# MARK-II_board.net
KiCad netlist of a schematic drawn in EAGLE
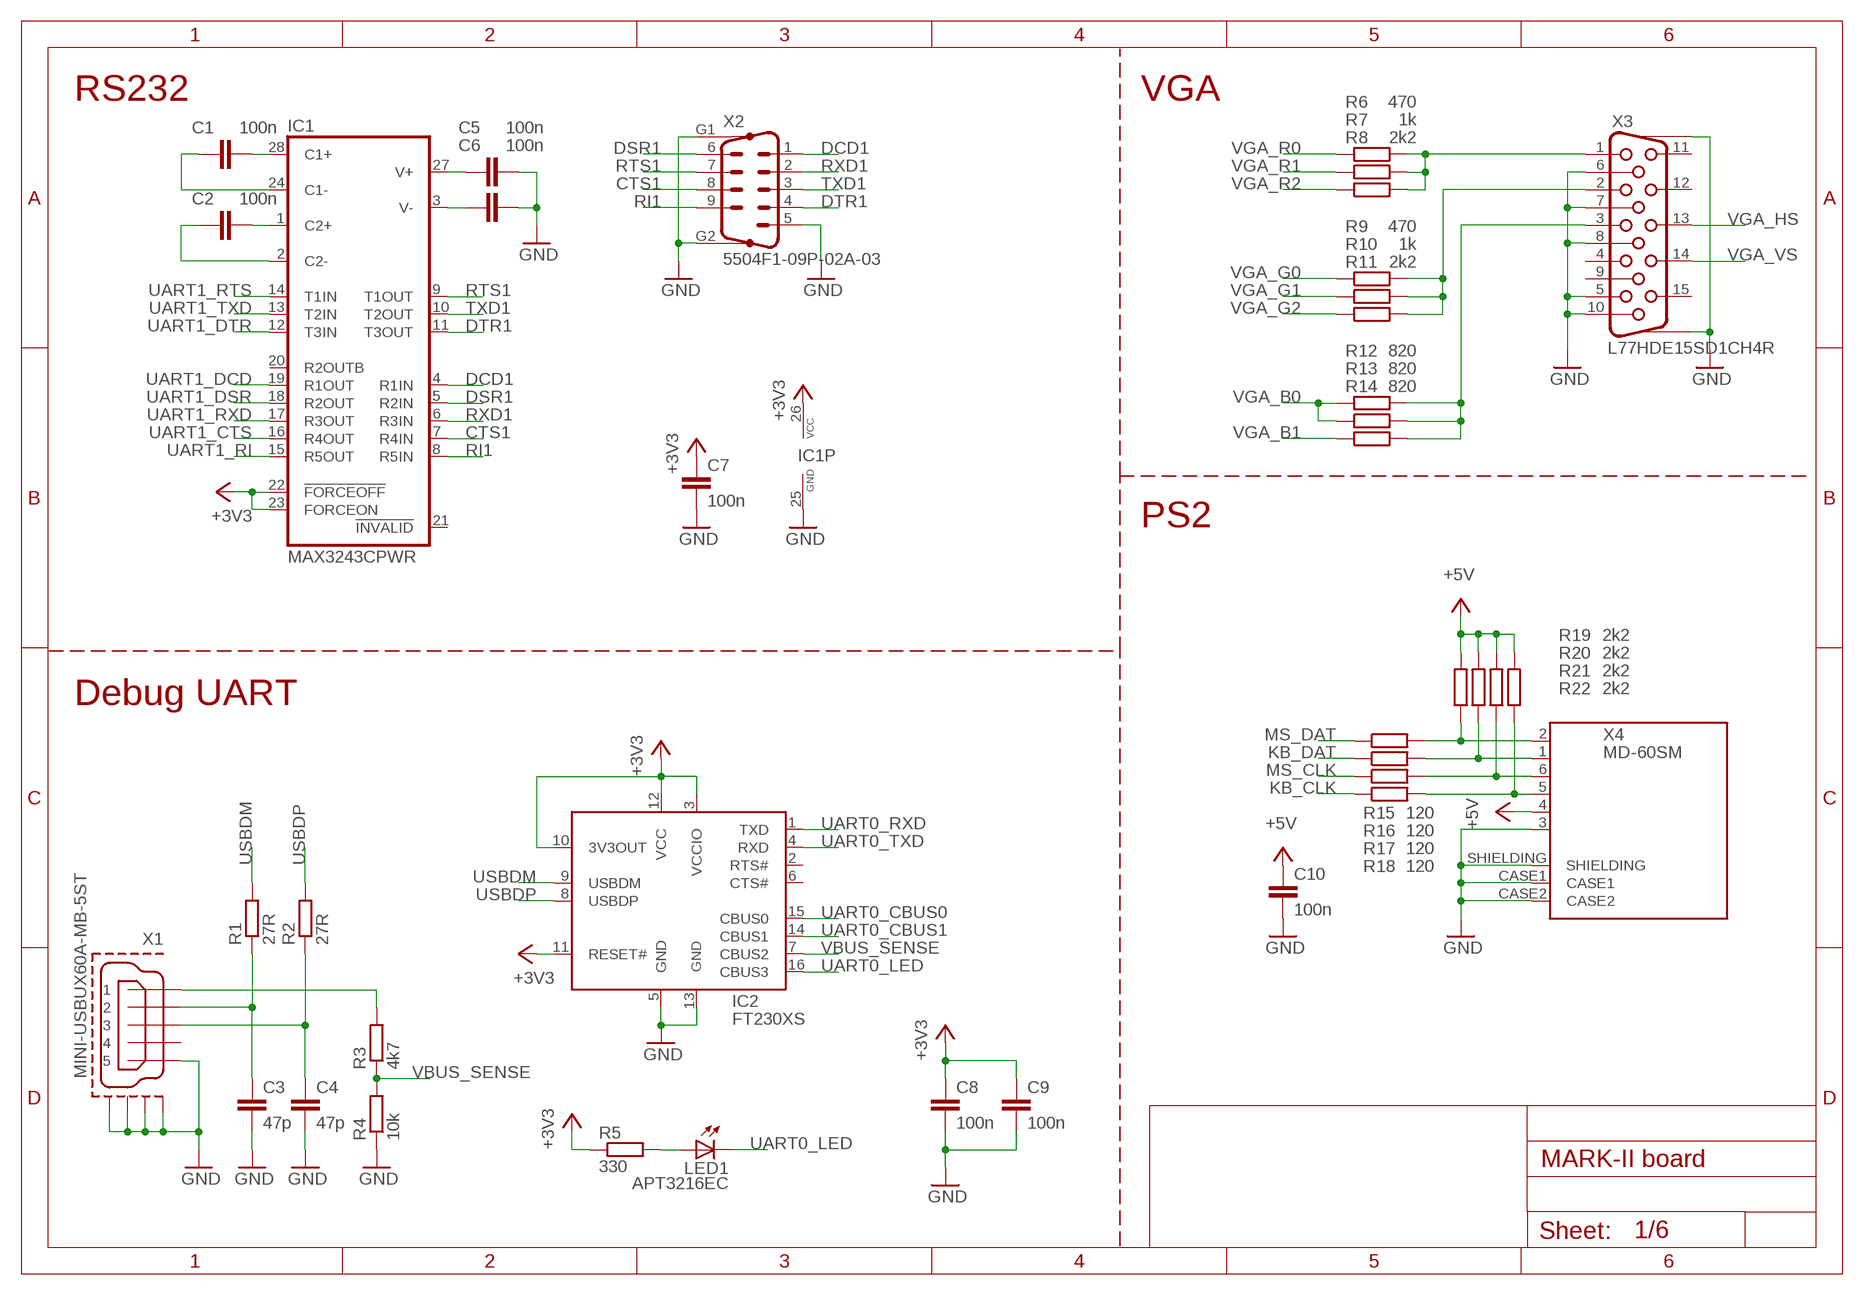
[diagram p0: schematic, sheet 1]
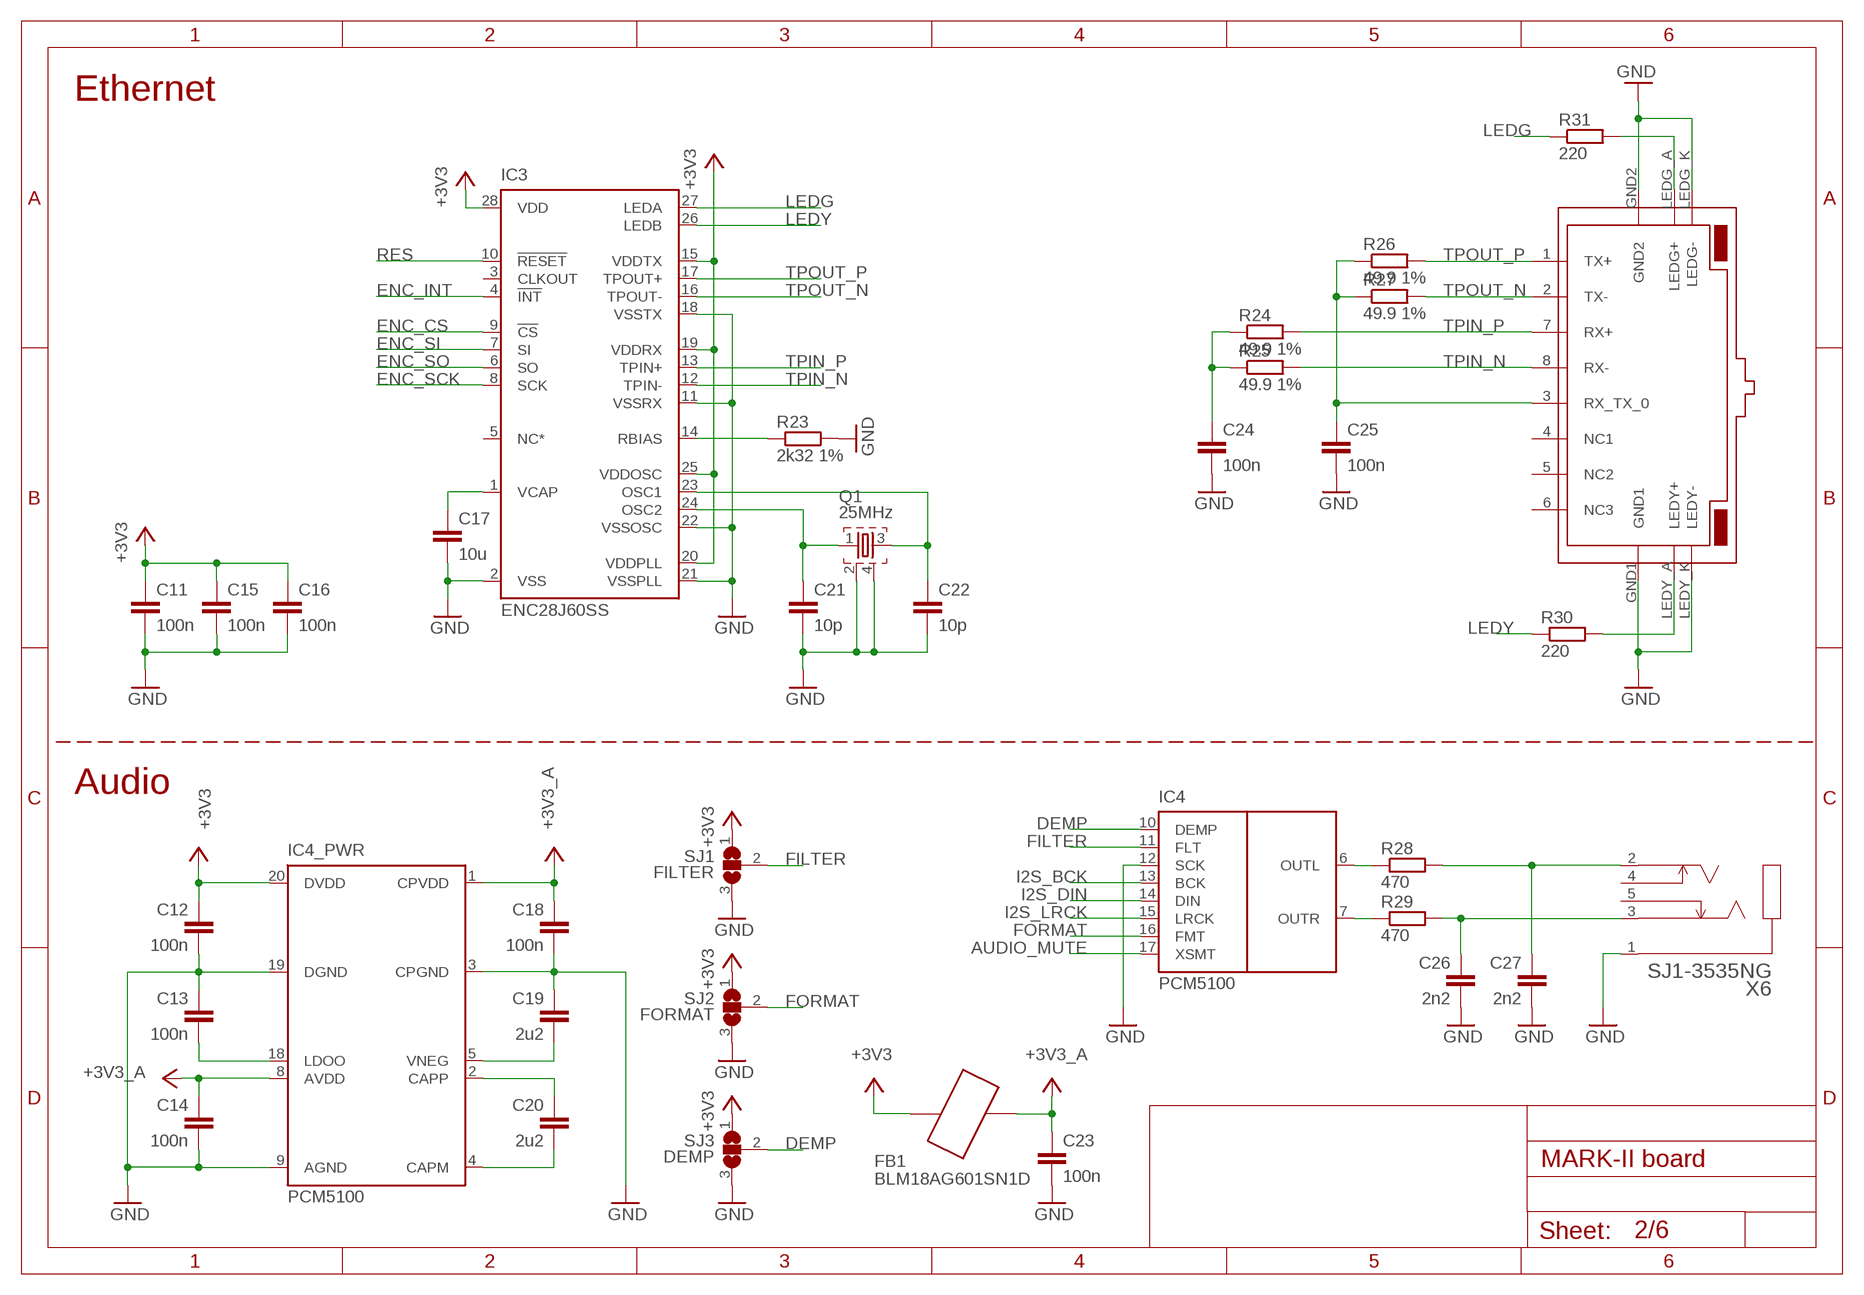
[diagram p1: schematic, sheet 2]
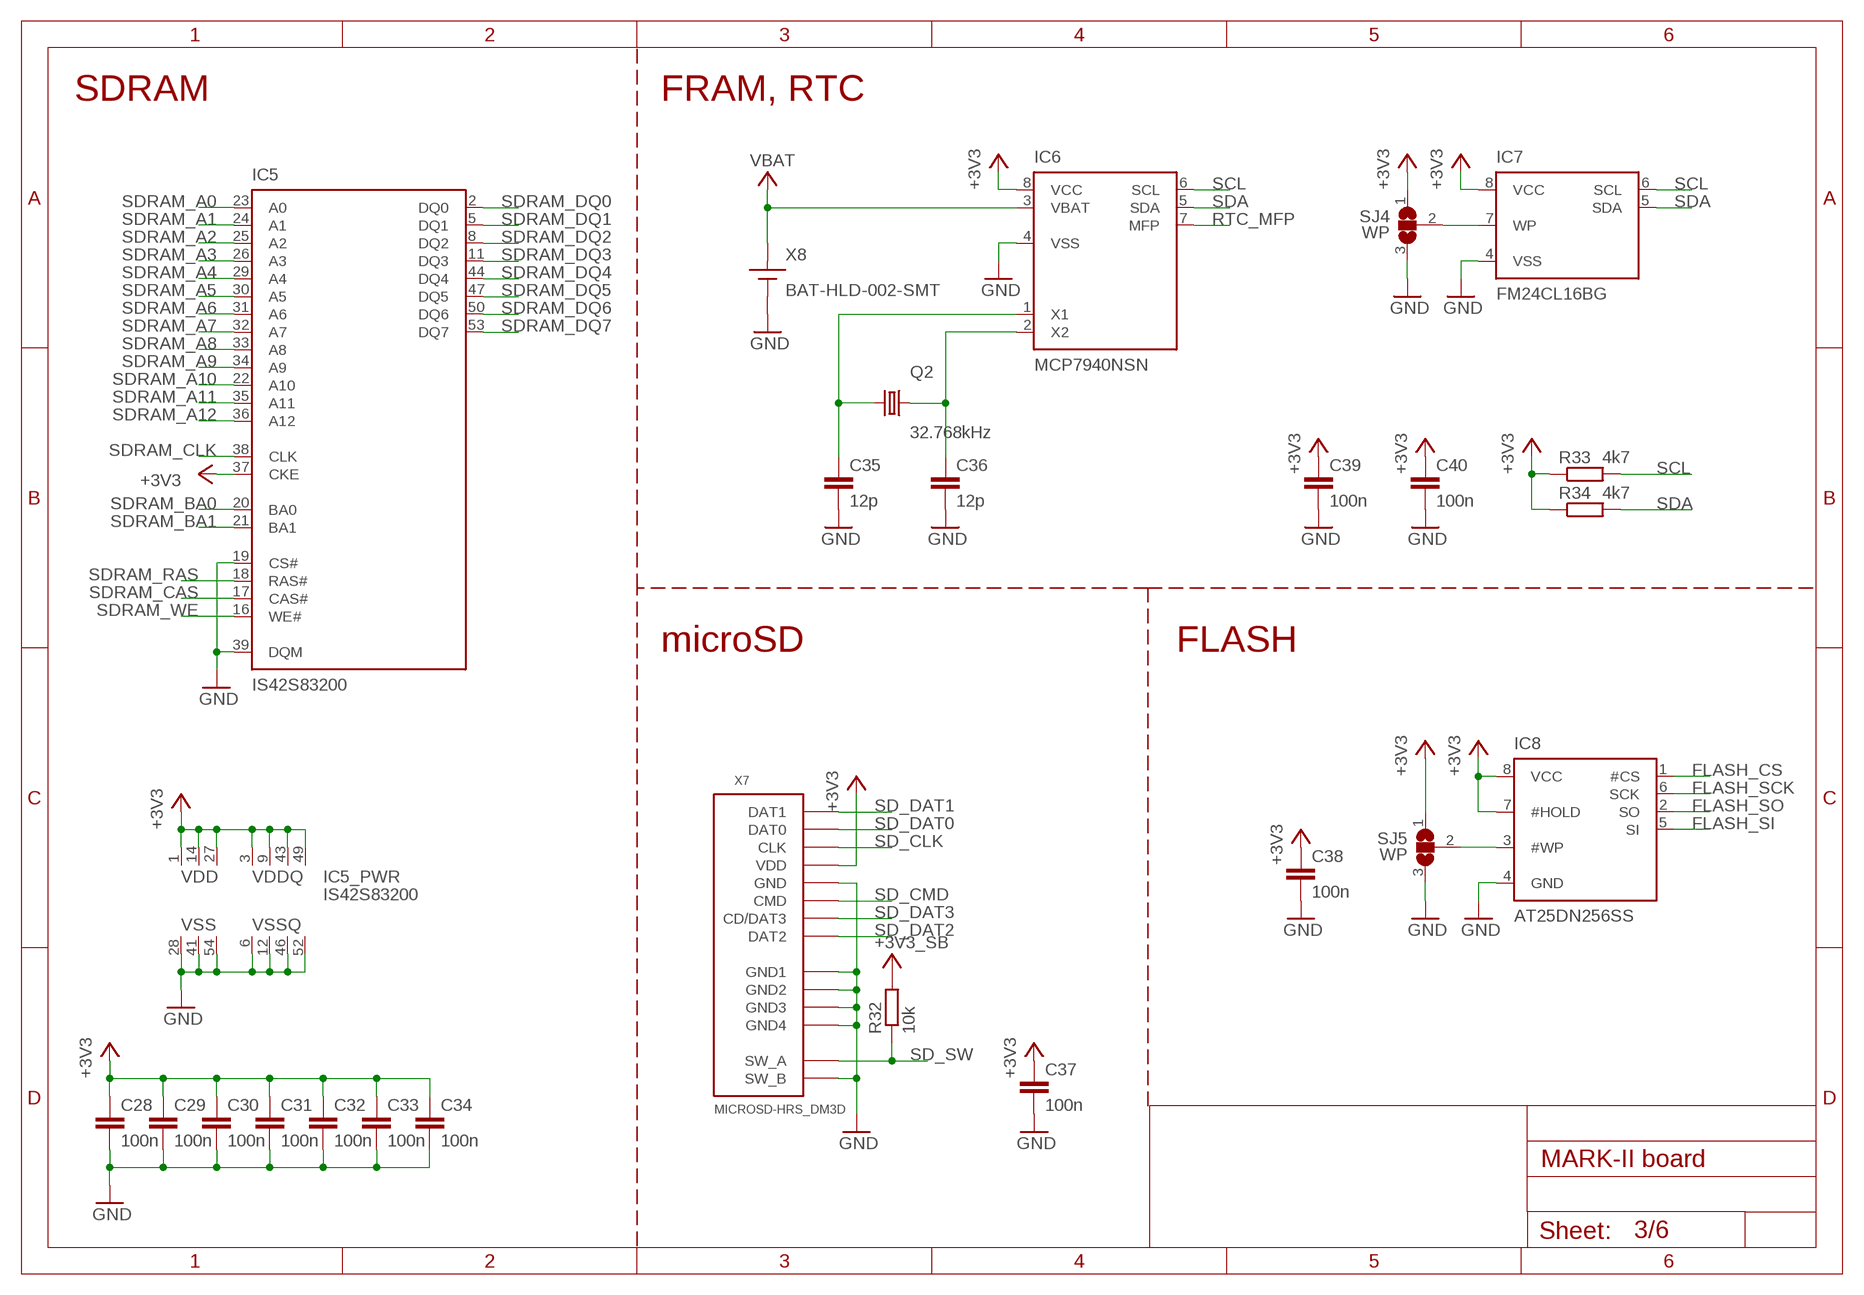
[diagram p2: schematic, sheet 3]
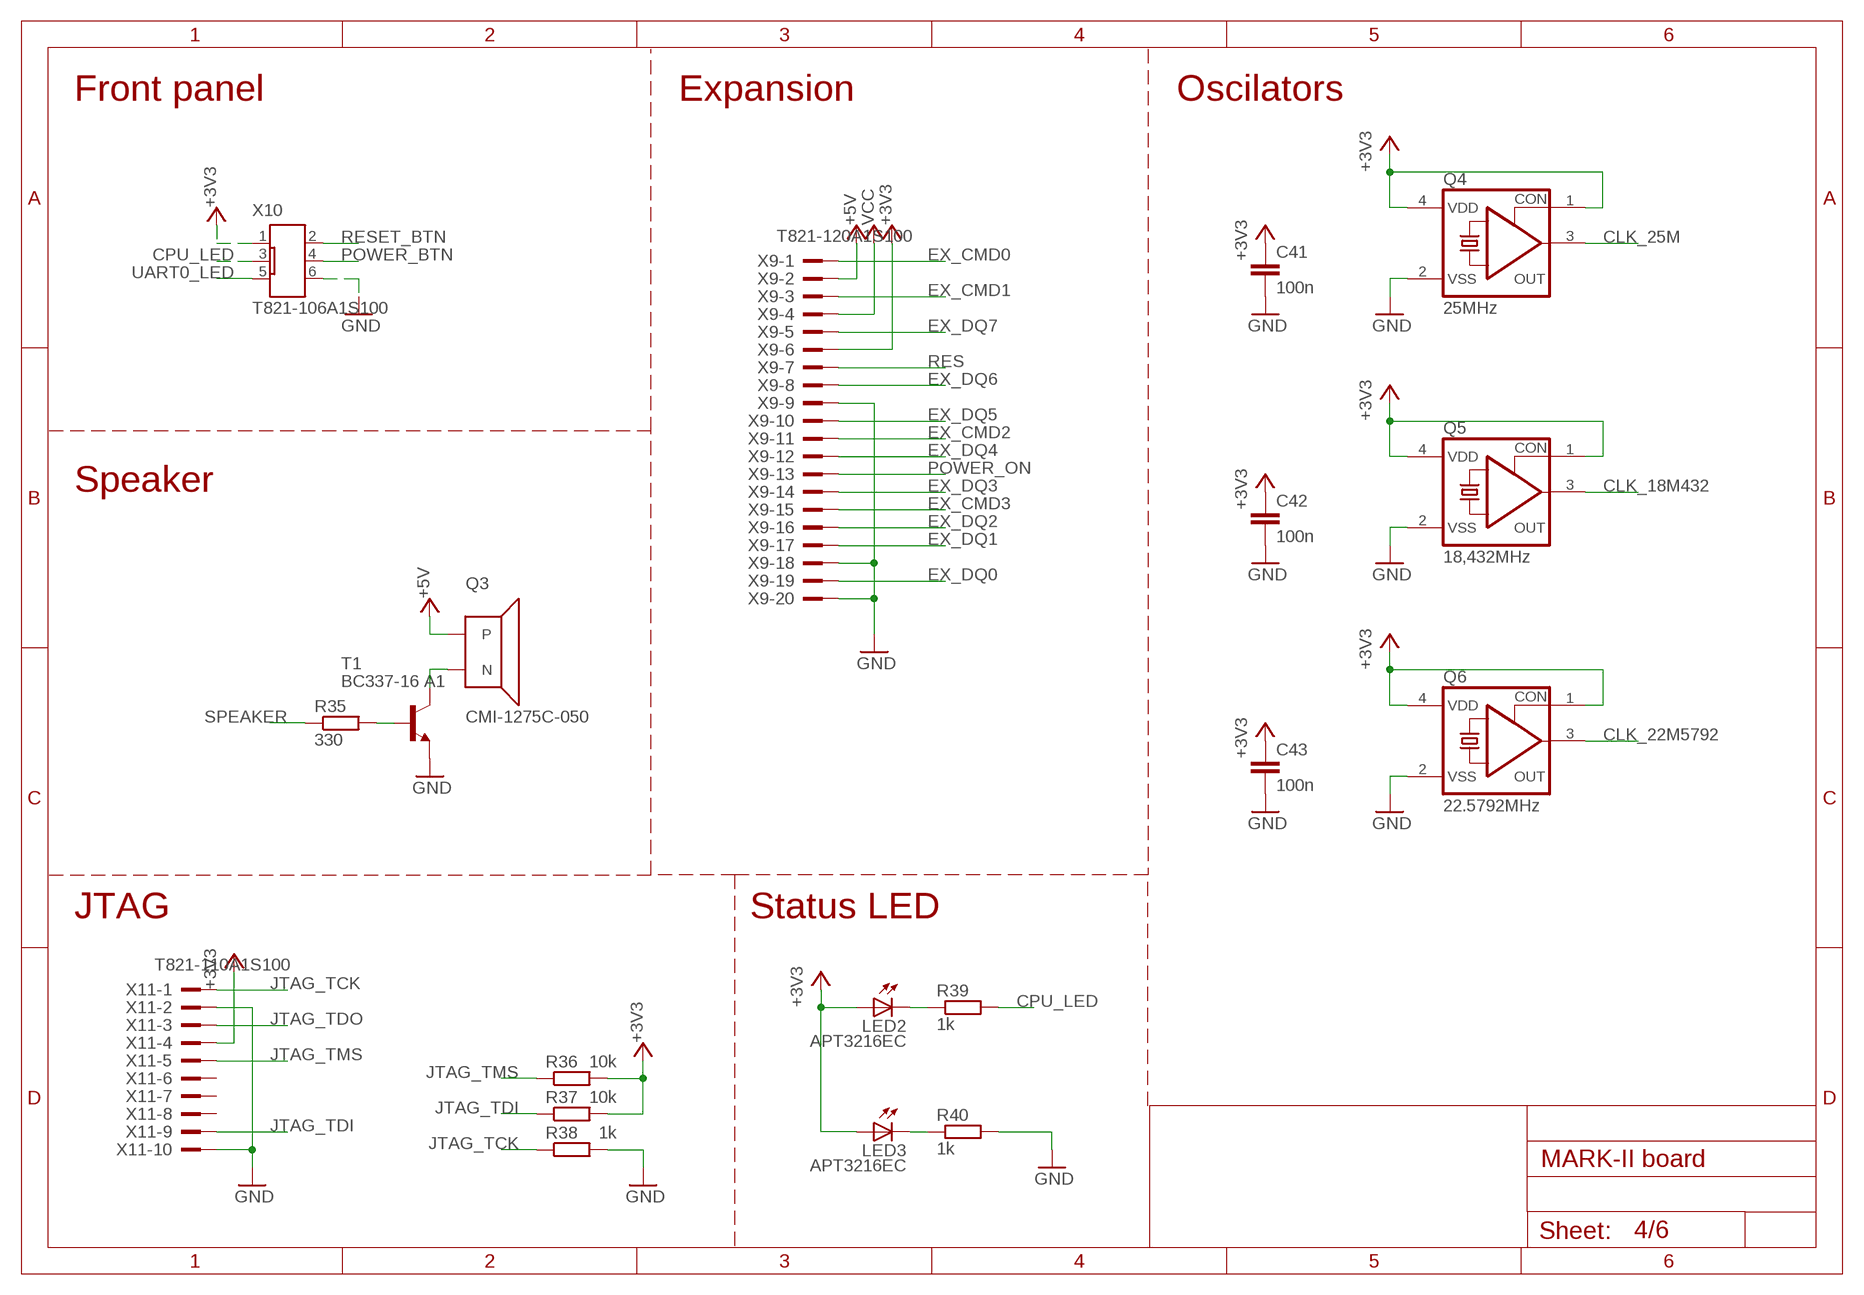
[diagram p3: schematic, sheet 4]
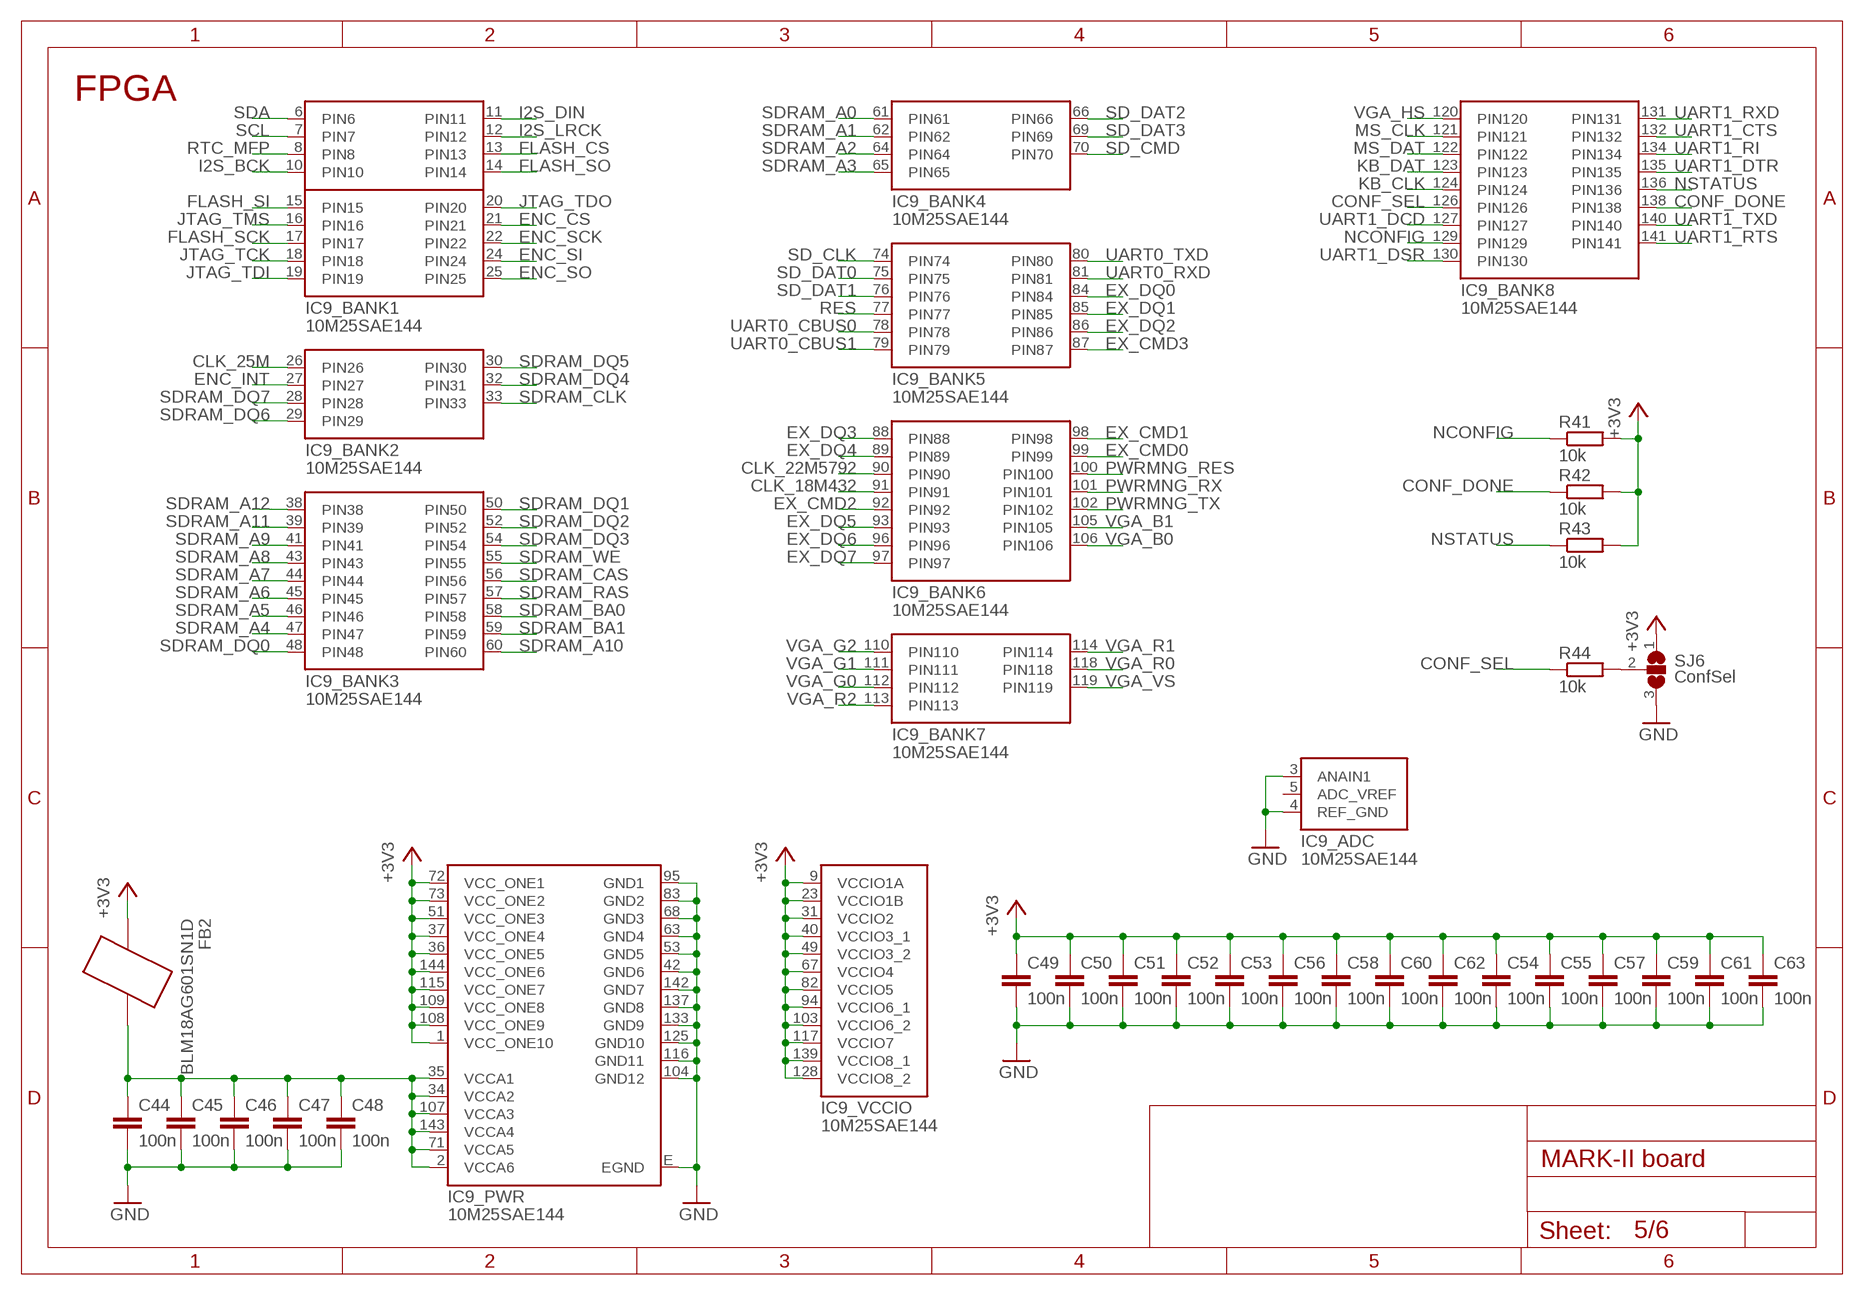
[diagram p4: schematic, sheet 5]
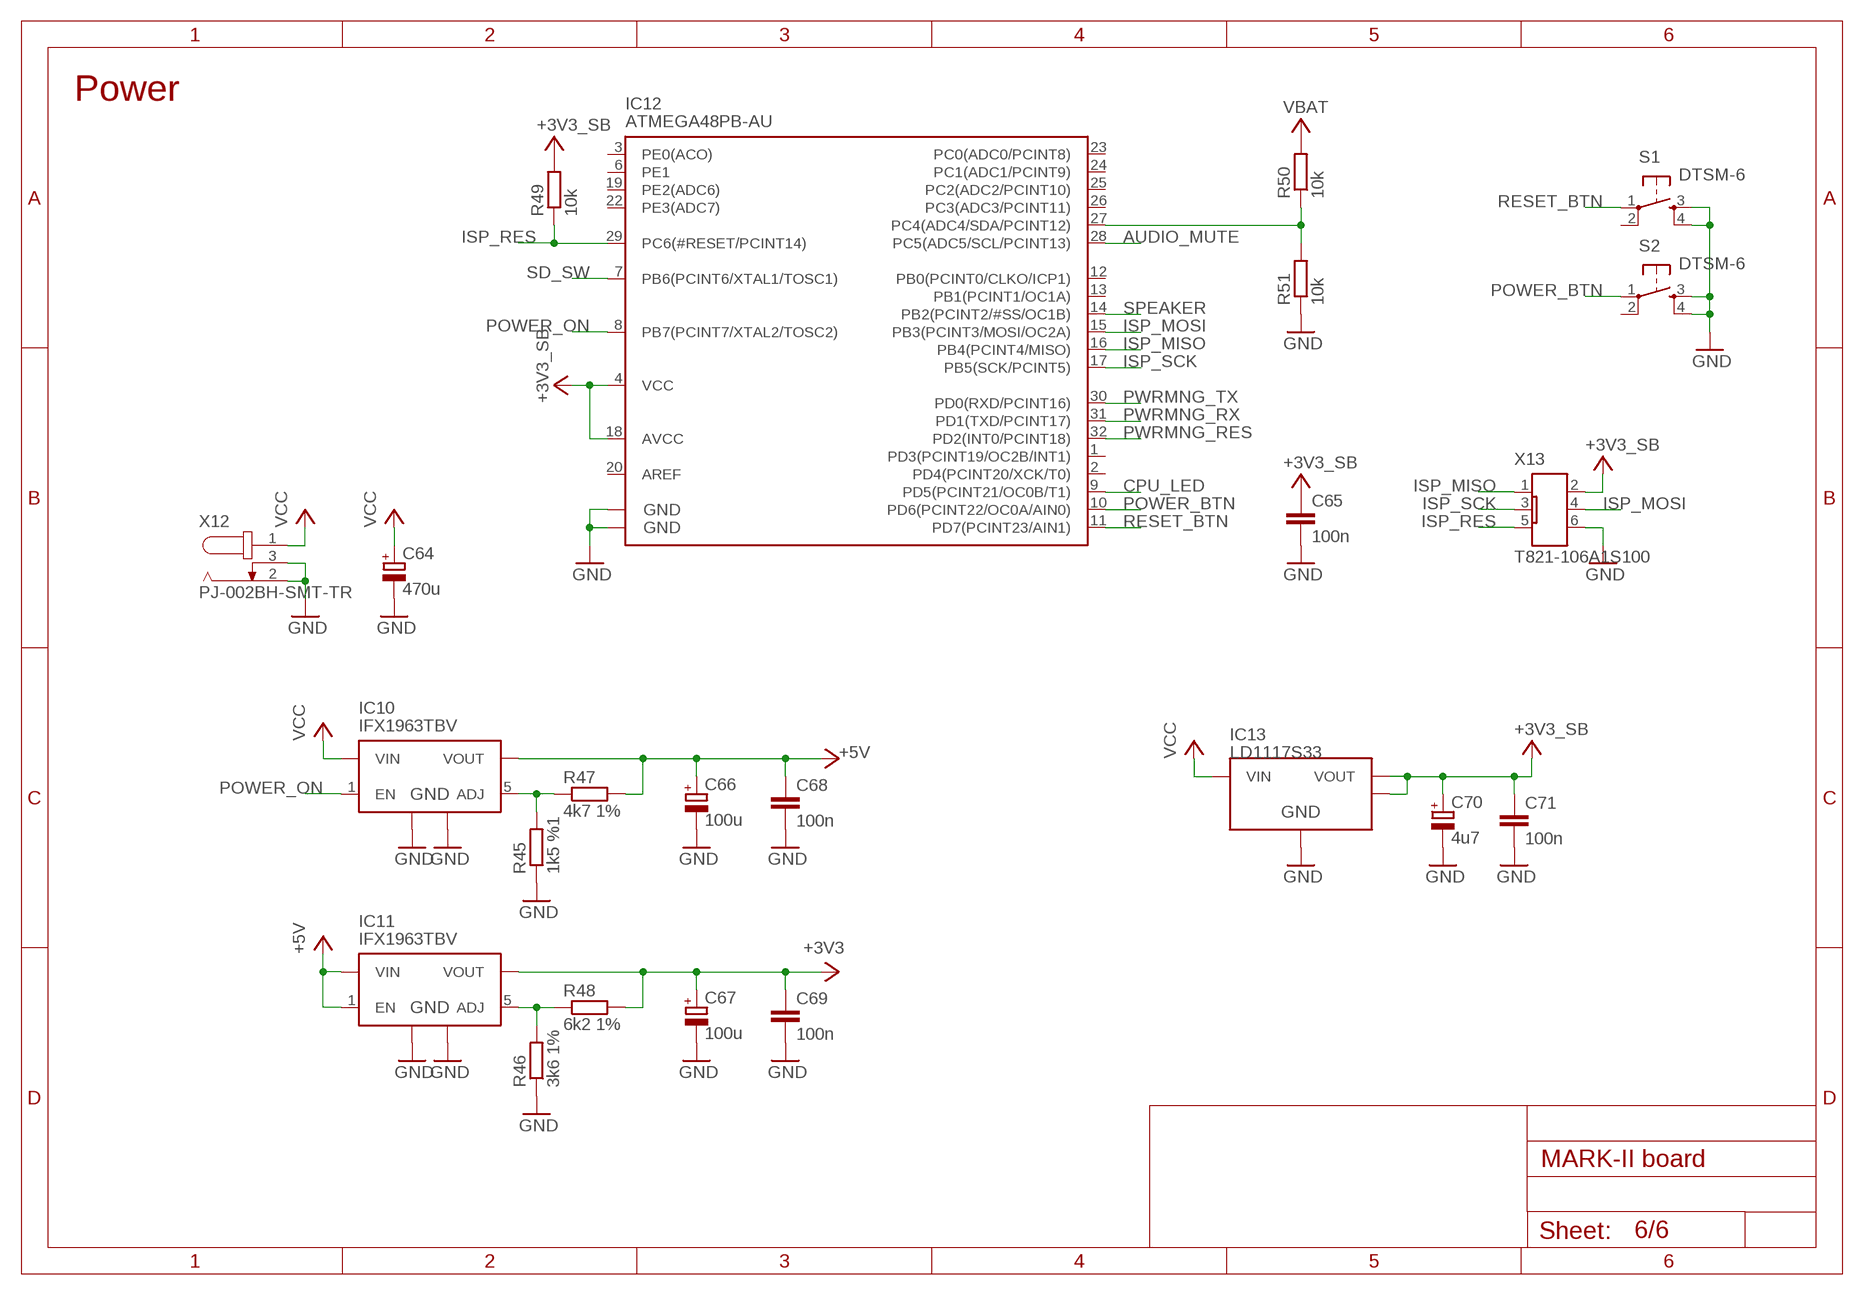
[diagram p5: schematic, sheet 6]

(export (version "E")
  (design (tool "Eeschema 10.0.6"))
  (components
    (comp (ref "C28")
      (value "100n")
      (footprint "eagle-import:C0603")
      (libsource (lib "eagle-import") (part "CC0603"))
    )
    (comp (ref "C29")
      (value "100n")
      (footprint "eagle-import:C0603")
      (libsource (lib "eagle-import") (part "CC0603"))
    )
    (comp (ref "C30")
      (value "100n")
      (footprint "eagle-import:C0603")
      (libsource (lib "eagle-import") (part "CC0603"))
    )
    (comp (ref "C31")
      (value "100n")
      (footprint "eagle-import:C0603")
      (libsource (lib "eagle-import") (part "CC0603"))
    )
    (comp (ref "C32")
      (value "100n")
      (footprint "eagle-import:C0603")
      (libsource (lib "eagle-import") (part "CC0603"))
    )
    (comp (ref "C33")
      (value "100n")
      (footprint "eagle-import:C0603")
      (libsource (lib "eagle-import") (part "CC0603"))
    )
    (comp (ref "C34")
      (value "100n")
      (footprint "eagle-import:C0603")
      (libsource (lib "eagle-import") (part "CC0603"))
    )
    (comp (ref "C35")
      (value "12p")
      (footprint "eagle-import:C0603")
      (libsource (lib "eagle-import") (part "CC0603"))
    )
    (comp (ref "C36")
      (value "12p")
      (footprint "eagle-import:C0603")
      (libsource (lib "eagle-import") (part "CC0603"))
    )
    (comp (ref "C37")
      (value "100n")
      (footprint "eagle-import:C0603")
      (libsource (lib "eagle-import") (part "CC0603"))
    )
    (comp (ref "C38")
      (value "100n")
      (footprint "eagle-import:C0603")
      (libsource (lib "eagle-import") (part "CC0603"))
    )
    (comp (ref "C39")
      (value "100n")
      (footprint "eagle-import:C0603")
      (libsource (lib "eagle-import") (part "CC0603"))
    )
    (comp (ref "C40")
      (value "100n")
      (footprint "eagle-import:C0603")
      (libsource (lib "eagle-import") (part "CC0603"))
    )
    (comp (ref "IC5")
      (value "IS42S83200")
      (footprint "eagle-import:TSOP54")
      (fields (field (name "MOUSER") "913-AS4C32M8SA6TIN"))
      (libsource (lib "eagle-import") (part "IS42S83200"))
    )
    (comp (ref "IC6")
      (value "MCP7940NSN")
      (footprint "eagle-import:SOIC8")
      (libsource (lib "eagle-import") (part "MCP7940NSN"))
    )
    (comp (ref "IC7")
      (value "FM24CL16BG")
      (footprint "eagle-import:SOIC8")
      (libsource (lib "eagle-import") (part "FM24CL16BG"))
    )
    (comp (ref "IC8")
      (value "AT25DN256SS")
      (footprint "eagle-import:SOIC8")
      (libsource (lib "eagle-import") (part "AT25DN256SS"))
    )
    (comp (ref "Q2")
      (value "32.768kHz")
      (footprint "eagle-import:85SMX")
      (libsource (lib "eagle-import") (part "CRYSTALS-NOGND-85SMX"))
    )
    (comp (ref "R32")
      (value "10k")
      (footprint "eagle-import:R0603")
      (libsource (lib "eagle-import") (part "RR0603"))
    )
    (comp (ref "R33")
      (value "4k7")
      (footprint "eagle-import:R0603")
      (libsource (lib "eagle-import") (part "RR0603"))
    )
    (comp (ref "R34")
      (value "4k7")
      (footprint "eagle-import:R0603")
      (libsource (lib "eagle-import") (part "RR0603"))
    )
    (comp (ref "SJ4")
      (value "WP")
      (footprint "eagle-import:SJ_2")
      (libsource (lib "eagle-import") (part "SJ2W"))
    )
    (comp (ref "SJ5")
      (value "WP")
      (footprint "eagle-import:SJ_2")
      (libsource (lib "eagle-import") (part "SJ2W"))
    )
    (comp (ref "X7")
      (value "MICROSD-HRS_DM3D")
      (footprint "eagle-import:DM3D")
      (libsource (lib "eagle-import") (part "MICROSD-HRS_DM3D"))
    )
    (comp (ref "X8")
      (value "BAT-HLD-002-SMT")
      (footprint "eagle-import:BAT-HLD-002-SMT")
      (libsource (lib "eagle-import") (part "BAT-HLD-002-SMT"))
    )
    (comp (ref "C41")
      (value "100n")
      (footprint "eagle-import:C0603")
      (libsource (lib "eagle-import") (part "CC0603"))
    )
    (comp (ref "C42")
      (value "100n")
      (footprint "eagle-import:C0603")
      (libsource (lib "eagle-import") (part "CC0603"))
    )
    (comp (ref "C43")
      (value "100n")
      (footprint "eagle-import:C0603")
      (libsource (lib "eagle-import") (part "CC0603"))
    )
    (comp (ref "LED2")
      (value "APT3216EC")
      (footprint "eagle-import:1206")
      (libsource (lib "eagle-import") (part "LEDSMD"))
    )
    (comp (ref "LED3")
      (value "APT3216EC")
      (footprint "eagle-import:1206")
      (libsource (lib "eagle-import") (part "LEDSMD"))
    )
    (comp (ref "Q3")
      (value "CMI-1275C-050")
      (footprint "eagle-import:BUUZZER")
      (libsource (lib "eagle-import") (part "CMI-1275C-050"))
    )
    (comp (ref "Q4")
      (value "25MHz")
      (footprint "eagle-import:5.2X3.4-4-PAD")
      (libsource (lib "eagle-import") (part "OSC-OE-CFPS-9"))
    )
    (comp (ref "Q5")
      (value "18,432MHz")
      (footprint "eagle-import:5.2X3.4-4-PAD")
      (libsource (lib "eagle-import") (part "OSC-OE-CFPS-9"))
    )
    (comp (ref "Q6")
      (value "22.5792MHz")
      (footprint "eagle-import:5.2X3.4-4-PAD")
      (libsource (lib "eagle-import") (part "OSC-OE-CFPS-9"))
    )
    (comp (ref "R35")
      (value "330")
      (footprint "eagle-import:R0603")
      (libsource (lib "eagle-import") (part "RR0603"))
    )
    (comp (ref "R36")
      (value "10k")
      (footprint "eagle-import:R0603")
      (libsource (lib "eagle-import") (part "RR0603"))
    )
    (comp (ref "R37")
      (value "10k")
      (footprint "eagle-import:R0603")
      (libsource (lib "eagle-import") (part "RR0603"))
    )
    (comp (ref "R38")
      (value "1k")
      (footprint "eagle-import:R0603")
      (libsource (lib "eagle-import") (part "RR0603"))
    )
    (comp (ref "R39")
      (value "1k")
      (footprint "eagle-import:R0603")
      (libsource (lib "eagle-import") (part "RR0603"))
    )
    (comp (ref "R40")
      (value "1k")
      (footprint "eagle-import:R0603")
      (libsource (lib "eagle-import") (part "RR0603"))
    )
    (comp (ref "T1")
      (value "BC337-16 A1")
      (footprint "eagle-import:TO92")
      (libsource (lib "eagle-import") (part "BC337"))
    )
    (comp (ref "X9")
      (value "T821-120A1S100")
      (footprint "eagle-import:PAK100_2500-20")
      (fields (field (name "FARNELL") "2215309"))
      (libsource (lib "eagle-import") (part "2520-"))
    )
    (comp (ref "X10")
      (value "T821-106A1S100")
      (footprint "eagle-import:PAK100_2300-06")
      (libsource (lib "eagle-import") (part "IDC_2306"))
    )
    (comp (ref "X11")
      (value "T821-110A1S100")
      (footprint "eagle-import:PAK100_2500-10")
      (fields (field (name "FARNELL") "2215304"))
      (libsource (lib "eagle-import") (part "2510-"))
    )
    (comp (ref "C44")
      (value "100n")
      (footprint "eagle-import:C0603")
      (libsource (lib "eagle-import") (part "CC0603"))
    )
    (comp (ref "C45")
      (value "100n")
      (footprint "eagle-import:C0603")
      (libsource (lib "eagle-import") (part "CC0603"))
    )
    (comp (ref "C46")
      (value "100n")
      (footprint "eagle-import:C0603")
      (libsource (lib "eagle-import") (part "CC0603"))
    )
    (comp (ref "C47")
      (value "100n")
      (footprint "eagle-import:C0603")
      (libsource (lib "eagle-import") (part "CC0603"))
    )
    (comp (ref "C48")
      (value "100n")
      (footprint "eagle-import:C0603")
      (libsource (lib "eagle-import") (part "CC0603"))
    )
    (comp (ref "C49")
      (value "100n")
      (footprint "eagle-import:C0603")
      (libsource (lib "eagle-import") (part "CC0603"))
    )
    (comp (ref "C50")
      (value "100n")
      (footprint "eagle-import:C0603")
      (libsource (lib "eagle-import") (part "CC0603"))
    )
    (comp (ref "C51")
      (value "100n")
      (footprint "eagle-import:C0603")
      (libsource (lib "eagle-import") (part "CC0603"))
    )
    (comp (ref "C52")
      (value "100n")
      (footprint "eagle-import:C0603")
      (libsource (lib "eagle-import") (part "CC0603"))
    )
    (comp (ref "C53")
      (value "100n")
      (footprint "eagle-import:C0603")
      (libsource (lib "eagle-import") (part "CC0603"))
    )
    (comp (ref "C54")
      (value "100n")
      (footprint "eagle-import:C0603")
      (libsource (lib "eagle-import") (part "CC0603"))
    )
    (comp (ref "C55")
      (value "100n")
      (footprint "eagle-import:C0603")
      (libsource (lib "eagle-import") (part "CC0603"))
    )
    (comp (ref "C56")
      (value "100n")
      (footprint "eagle-import:C0603")
      (libsource (lib "eagle-import") (part "CC0603"))
    )
    (comp (ref "C57")
      (value "100n")
      (footprint "eagle-import:C0603")
      (libsource (lib "eagle-import") (part "CC0603"))
    )
    (comp (ref "C58")
      (value "100n")
      (footprint "eagle-import:C0603")
      (libsource (lib "eagle-import") (part "CC0603"))
    )
    (comp (ref "C59")
      (value "100n")
      (footprint "eagle-import:C0603")
      (libsource (lib "eagle-import") (part "CC0603"))
    )
    (comp (ref "C60")
      (value "100n")
      (footprint "eagle-import:C0603")
      (libsource (lib "eagle-import") (part "CC0603"))
    )
    (comp (ref "C61")
      (value "100n")
      (footprint "eagle-import:C0603")
      (libsource (lib "eagle-import") (part "CC0603"))
    )
    (comp (ref "C62")
      (value "100n")
      (footprint "eagle-import:C0603")
      (libsource (lib "eagle-import") (part "CC0603"))
    )
    (comp (ref "C63")
      (value "100n")
      (footprint "eagle-import:C0603")
      (libsource (lib "eagle-import") (part "CC0603"))
    )
    (comp (ref "FB2")
      (value "BLM18AG601SN1D")
      (footprint "eagle-import:R0603")
      (libsource (lib "eagle-import") (part "FERRITE_BEAD603"))
    )
    (comp (ref "IC9")
      (value "10M25SAE144")
      (footprint "eagle-import:EQFP144")
      (fields (field (name "MOUSER") "989-10M25SAE144C8G"))
      (libsource (lib "eagle-import") (part "10M25SAE144"))
    )
    (comp (ref "R41")
      (value "10k")
      (footprint "eagle-import:R0603")
      (libsource (lib "eagle-import") (part "RR0603"))
    )
    (comp (ref "R42")
      (value "10k")
      (footprint "eagle-import:R0603")
      (libsource (lib "eagle-import") (part "RR0603"))
    )
    (comp (ref "R43")
      (value "10k")
      (footprint "eagle-import:R0603")
      (libsource (lib "eagle-import") (part "RR0603"))
    )
    (comp (ref "R44")
      (value "10k")
      (footprint "eagle-import:R0603")
      (libsource (lib "eagle-import") (part "RR0603"))
    )
    (comp (ref "SJ6")
      (value "ConfSel")
      (footprint "eagle-import:SJ_2")
      (libsource (lib "eagle-import") (part "SJ2W"))
    )
    (comp (ref "C11")
      (value "100n")
      (footprint "eagle-import:C0603")
      (libsource (lib "eagle-import") (part "CC0603"))
    )
    (comp (ref "C12")
      (value "100n")
      (footprint "eagle-import:C0603")
      (libsource (lib "eagle-import") (part "CC0603"))
    )
    (comp (ref "C13")
      (value "100n")
      (footprint "eagle-import:C0603")
      (libsource (lib "eagle-import") (part "CC0603"))
    )
    (comp (ref "C14")
      (value "100n")
      (footprint "eagle-import:C0603")
      (libsource (lib "eagle-import") (part "CC0603"))
    )
    (comp (ref "C15")
      (value "100n")
      (footprint "eagle-import:C0603")
      (libsource (lib "eagle-import") (part "CC0603"))
    )
    (comp (ref "C16")
      (value "100n")
      (footprint "eagle-import:C0603")
      (libsource (lib "eagle-import") (part "CC0603"))
    )
    (comp (ref "C17")
      (value "10u")
      (footprint "eagle-import:C0603")
      (libsource (lib "eagle-import") (part "CC0603"))
    )
    (comp (ref "C18")
      (value "100n")
      (footprint "eagle-import:C0603")
      (libsource (lib "eagle-import") (part "CC0603"))
    )
    (comp (ref "C19")
      (value "2u2")
      (footprint "eagle-import:C0603")
      (libsource (lib "eagle-import") (part "CC0603"))
    )
    (comp (ref "C20")
      (value "2u2")
      (footprint "eagle-import:C0603")
      (libsource (lib "eagle-import") (part "CC0603"))
    )
    (comp (ref "C21")
      (value "10p")
      (footprint "eagle-import:C0603")
      (libsource (lib "eagle-import") (part "CC0603"))
    )
    (comp (ref "C22")
      (value "10p")
      (footprint "eagle-import:C0603")
      (libsource (lib "eagle-import") (part "CC0603"))
    )
    (comp (ref "C23")
      (value "100n")
      (footprint "eagle-import:C0603")
      (libsource (lib "eagle-import") (part "CC0603"))
    )
    (comp (ref "C24")
      (value "100n")
      (footprint "eagle-import:C0603")
      (libsource (lib "eagle-import") (part "CC0603"))
    )
    (comp (ref "C25")
      (value "100n")
      (footprint "eagle-import:C0603")
      (libsource (lib "eagle-import") (part "CC0603"))
    )
    (comp (ref "C26")
      (value "2n2")
      (footprint "eagle-import:C0603")
      (libsource (lib "eagle-import") (part "CC0603"))
    )
    (comp (ref "C27")
      (value "2n2")
      (footprint "eagle-import:C0603")
      (libsource (lib "eagle-import") (part "CC0603"))
    )
    (comp (ref "FB1")
      (value "BLM18AG601SN1D")
      (footprint "eagle-import:R0603")
      (libsource (lib "eagle-import") (part "FERRITE_BEAD603"))
    )
    (comp (ref "IC3")
      (value "ENC28J60SS")
      (footprint "eagle-import:SSOP28")
      (libsource (lib "eagle-import") (part "ENC28J60SS"))
    )
    (comp (ref "IC4")
      (value "PCM5100")
      (footprint "eagle-import:TSSOP20")
      (fields (field (name "MOUSER") "595-PCM5100APWR"))
      (libsource (lib "eagle-import") (part "PCM5100"))
    )
    (comp (ref "Q1")
      (value "25MHz")
      (footprint "eagle-import:3.4X2.7-4-PAD")
      (libsource (lib "eagle-import") (part "CRYSTALS-GND-LID-CFPX-180"))
    )
    (comp (ref "R23")
      (value "2k32 1%")
      (footprint "eagle-import:R0603")
      (libsource (lib "eagle-import") (part "RR0603"))
    )
    (comp (ref "R24")
      (value "49.9 1%")
      (footprint "eagle-import:R0603")
      (libsource (lib "eagle-import") (part "RR0603"))
    )
    (comp (ref "R25")
      (value "49.9 1%")
      (footprint "eagle-import:R0603")
      (libsource (lib "eagle-import") (part "RR0603"))
    )
    (comp (ref "R26")
      (value "49.9 1%")
      (footprint "eagle-import:R0603")
      (libsource (lib "eagle-import") (part "RR0603"))
    )
    (comp (ref "R27")
      (value "49.9 1%")
      (footprint "eagle-import:R0603")
      (libsource (lib "eagle-import") (part "RR0603"))
    )
    (comp (ref "R28")
      (value "470")
      (footprint "eagle-import:R0603")
      (libsource (lib "eagle-import") (part "RR0603"))
    )
    (comp (ref "R29")
      (value "470")
      (footprint "eagle-import:R0603")
      (libsource (lib "eagle-import") (part "RR0603"))
    )
    (comp (ref "R30")
      (value "220")
      (footprint "eagle-import:R0603")
      (libsource (lib "eagle-import") (part "RR0603"))
    )
    (comp (ref "R31")
      (value "220")
      (footprint "eagle-import:R0603")
      (libsource (lib "eagle-import") (part "RR0603"))
    )
    (comp (ref "SJ1")
      (value "FILTER")
      (footprint "eagle-import:SJ_2")
      (libsource (lib "eagle-import") (part "SJ2W"))
    )
    (comp (ref "SJ2")
      (value "FORMAT")
      (footprint "eagle-import:SJ_2")
      (libsource (lib "eagle-import") (part "SJ2W"))
    )
    (comp (ref "SJ3")
      (value "DEMP")
      (footprint "eagle-import:SJ_2")
      (libsource (lib "eagle-import") (part "SJ2W"))
    )
    (comp (ref "X5")
      (value "RB1-125BAG1A")
      (footprint "eagle-import:RB1-125BAG1A")
      (libsource (lib "eagle-import") (part "RB1-125BAG1A"))
    )
    (comp (ref "X6")
      (value "SJ1-3535NG")
      (footprint "eagle-import:JACK")
      (libsource (lib "eagle-import") (part "SJ1-3535NG"))
    )
    (comp (ref "C64")
      (value "470u")
      (footprint "eagle-import:E3,5-8")
      (libsource (lib "eagle-import") (part "C-POLE3.5-8"))
    )
    (comp (ref "C65")
      (value "100n")
      (footprint "eagle-import:C0603")
      (libsource (lib "eagle-import") (part "CC0603"))
    )
    (comp (ref "C66")
      (value "100u")
      (footprint "eagle-import:E2,5-7")
      (libsource (lib "eagle-import") (part "C-POLE2.5-7"))
    )
    (comp (ref "C67")
      (value "100u")
      (footprint "eagle-import:E2,5-7")
      (libsource (lib "eagle-import") (part "C-POLE2.5-7"))
    )
    (comp (ref "C68")
      (value "100n")
      (footprint "eagle-import:C0603")
      (libsource (lib "eagle-import") (part "CC0603"))
    )
    (comp (ref "C69")
      (value "100n")
      (footprint "eagle-import:C0603")
      (libsource (lib "eagle-import") (part "CC0603"))
    )
    (comp (ref "C70")
      (value "4u7")
      (footprint "eagle-import:E2,5-5")
      (libsource (lib "eagle-import") (part "C-POLE2.5-5"))
    )
    (comp (ref "C71")
      (value "100n")
      (footprint "eagle-import:C0603")
      (libsource (lib "eagle-import") (part "CC0603"))
    )
    (comp (ref "IC10")
      (value "IFX1963TBV")
      (footprint "eagle-import:D2PAK-5")
      (libsource (lib "eagle-import") (part "IFX1963TBV"))
    )
    (comp (ref "IC11")
      (value "IFX1963TBV")
      (footprint "eagle-import:D2PAK-5")
      (libsource (lib "eagle-import") (part "IFX1963TBV"))
    )
    (comp (ref "IC12")
      (value "ATMEGA48PB-AU")
      (footprint "eagle-import:TQFP32-08")
      (libsource (lib "eagle-import") (part "ATMEGA48PB-AU"))
    )
    (comp (ref "IC13")
      (value "LD1117S33")
      (footprint "eagle-import:SOT223")
      (libsource (lib "eagle-import") (part "LD1117S33"))
    )
    (comp (ref "R45")
      (value "1k5 %1")
      (footprint "eagle-import:R0603")
      (libsource (lib "eagle-import") (part "RR0603"))
    )
    (comp (ref "R46")
      (value "3k6 1%")
      (footprint "eagle-import:R0603")
      (libsource (lib "eagle-import") (part "RR0603"))
    )
    (comp (ref "R47")
      (value "4k7 1%")
      (footprint "eagle-import:R0603")
      (libsource (lib "eagle-import") (part "RR0603"))
    )
    (comp (ref "R48")
      (value "6k2 1%")
      (footprint "eagle-import:R0603")
      (libsource (lib "eagle-import") (part "RR0603"))
    )
    (comp (ref "R49")
      (value "10k")
      (footprint "eagle-import:R0603")
      (libsource (lib "eagle-import") (part "RR0603"))
    )
    (comp (ref "R50")
      (value "10k")
      (footprint "eagle-import:R0603")
      (libsource (lib "eagle-import") (part "RR0603"))
    )
    (comp (ref "R51")
      (value "10k")
      (footprint "eagle-import:R0603")
      (libsource (lib "eagle-import") (part "RR0603"))
    )
    (comp (ref "S1")
      (value "DTSM-6")
      (footprint "eagle-import:DTSM-6")
      (libsource (lib "eagle-import") (part "DTSM-6"))
    )
    (comp (ref "S2")
      (value "DTSM-6")
      (footprint "eagle-import:DTSM-6")
      (libsource (lib "eagle-import") (part "DTSM-6"))
    )
    (comp (ref "X12")
      (value "PJ-002BH-SMT-TR")
      (footprint "eagle-import:PJ-002BH-SMT")
      (libsource (lib "eagle-import") (part "PJ-002BH-SMT"))
    )
    (comp (ref "X13")
      (value "T821-106A1S100")
      (footprint "eagle-import:PAK100_2300-06")
      (libsource (lib "eagle-import") (part "IDC_2306"))
    )
    (comp (ref "C1")
      (value "100n")
      (footprint "eagle-import:C0603")
      (libsource (lib "eagle-import") (part "CC0603"))
    )
    (comp (ref "C2")
      (value "100n")
      (footprint "eagle-import:C0603")
      (libsource (lib "eagle-import") (part "CC0603"))
    )
    (comp (ref "C3")
      (value "47p")
      (footprint "eagle-import:C0603")
      (libsource (lib "eagle-import") (part "CC0603"))
    )
    (comp (ref "C4")
      (value "47p")
      (footprint "eagle-import:C0603")
      (libsource (lib "eagle-import") (part "CC0603"))
    )
    (comp (ref "C5")
      (value "100n")
      (footprint "eagle-import:C0603")
      (libsource (lib "eagle-import") (part "CC0603"))
    )
    (comp (ref "C6")
      (value "100n")
      (footprint "eagle-import:C0603")
      (libsource (lib "eagle-import") (part "CC0603"))
    )
    (comp (ref "C7")
      (value "100n")
      (footprint "eagle-import:C0603")
      (libsource (lib "eagle-import") (part "CC0603"))
    )
    (comp (ref "C8")
      (value "100n")
      (footprint "eagle-import:C0603")
      (libsource (lib "eagle-import") (part "CC0603"))
    )
    (comp (ref "C9")
      (value "100n")
      (footprint "eagle-import:C0603")
      (libsource (lib "eagle-import") (part "CC0603"))
    )
    (comp (ref "C10")
      (value "100n")
      (footprint "eagle-import:C0603")
      (libsource (lib "eagle-import") (part "CC0603"))
    )
    (comp (ref "IC1")
      (value "MAX3243CPWR")
      (footprint "eagle-import:TSSOP28")
      (fields (field (name "MOUSER") "595-MAX3243CPWR"))
      (libsource (lib "eagle-import") (part "MAX3243UI"))
    )
    (comp (ref "IC2")
      (value "FT230XS")
      (footprint "eagle-import:SSOP16")
      (libsource (lib "eagle-import") (part "FT230XS"))
    )
    (comp (ref "LED1")
      (value "APT3216EC")
      (footprint "eagle-import:1206")
      (libsource (lib "eagle-import") (part "LEDSMD"))
    )
    (comp (ref "R1")
      (value "27R")
      (footprint "eagle-import:R0603")
      (libsource (lib "eagle-import") (part "RR0603"))
    )
    (comp (ref "R2")
      (value "27R")
      (footprint "eagle-import:R0603")
      (libsource (lib "eagle-import") (part "RR0603"))
    )
    (comp (ref "R3")
      (value "4k7")
      (footprint "eagle-import:R0603")
      (libsource (lib "eagle-import") (part "RR0603"))
    )
    (comp (ref "R4")
      (value "10k")
      (footprint "eagle-import:R0603")
      (libsource (lib "eagle-import") (part "RR0603"))
    )
    (comp (ref "R5")
      (value "330")
      (footprint "eagle-import:R0603")
      (libsource (lib "eagle-import") (part "RR0603"))
    )
    (comp (ref "R6")
      (value "470")
      (footprint "eagle-import:R0603")
      (libsource (lib "eagle-import") (part "RR0603"))
    )
    (comp (ref "R7")
      (value "1k")
      (footprint "eagle-import:R0603")
      (libsource (lib "eagle-import") (part "RR0603"))
    )
    (comp (ref "R8")
      (value "2k2")
      (footprint "eagle-import:R0603")
      (libsource (lib "eagle-import") (part "RR0603"))
    )
    (comp (ref "R9")
      (value "470")
      (footprint "eagle-import:R0603")
      (libsource (lib "eagle-import") (part "RR0603"))
    )
    (comp (ref "R10")
      (value "1k")
      (footprint "eagle-import:R0603")
      (libsource (lib "eagle-import") (part "RR0603"))
    )
    (comp (ref "R11")
      (value "2k2")
      (footprint "eagle-import:R0603")
      (libsource (lib "eagle-import") (part "RR0603"))
    )
    (comp (ref "R12")
      (value "820")
      (footprint "eagle-import:R0603")
      (libsource (lib "eagle-import") (part "RR0603"))
    )
    (comp (ref "R13")
      (value "820")
      (footprint "eagle-import:R0603")
      (libsource (lib "eagle-import") (part "RR0603"))
    )
    (comp (ref "R14")
      (value "820")
      (footprint "eagle-import:R0603")
      (libsource (lib "eagle-import") (part "RR0603"))
    )
    (comp (ref "R15")
      (value "120")
      (footprint "eagle-import:R0603")
      (libsource (lib "eagle-import") (part "RR0603"))
    )
    (comp (ref "R16")
      (value "120")
      (footprint "eagle-import:R0603")
      (libsource (lib "eagle-import") (part "RR0603"))
    )
    (comp (ref "R17")
      (value "120")
      (footprint "eagle-import:R0603")
      (libsource (lib "eagle-import") (part "RR0603"))
    )
    (comp (ref "R18")
      (value "120")
      (footprint "eagle-import:R0603")
      (libsource (lib "eagle-import") (part "RR0603"))
    )
    (comp (ref "R19")
      (value "2k2")
      (footprint "eagle-import:R0603")
      (libsource (lib "eagle-import") (part "RR0603"))
    )
    (comp (ref "R20")
      (value "2k2")
      (footprint "eagle-import:R0603")
      (libsource (lib "eagle-import") (part "RR0603"))
    )
    (comp (ref "R21")
      (value "2k2")
      (footprint "eagle-import:R0603")
      (libsource (lib "eagle-import") (part "RR0603"))
    )
    (comp (ref "R22")
      (value "2k2")
      (footprint "eagle-import:R0603")
      (libsource (lib "eagle-import") (part "RR0603"))
    )
    (comp (ref "X1")
      (value "MINI-USBUX60A-MB-5ST")
      (footprint "eagle-import:UX60A-MB-5ST")
      (libsource (lib "eagle-import") (part "MINI-USBUX60A-MB-5ST"))
    )
    (comp (ref "X2")
      (value "5504F1-09P-02A-03")
      (footprint "eagle-import:M09HP")
      (libsource (lib "eagle-import") (part "M09"))
    )
    (comp (ref "X3")
      (value "L77HDE15SD1CH4R")
      (footprint "eagle-import:HDF15H")
      (libsource (lib "eagle-import") (part "HF15H"))
    )
    (comp (ref "X4")
      (value "MD-60SM")
      (footprint "eagle-import:MINIDIN_6_3GND")
      (libsource (lib "eagle-import") (part "MINIDIN_6"))
    )
  )
  (nets
    (net (code "1") (name "+3V3") (class "Default")
      (node (ref "C11") (pin "1") (pinfunction "1_1") (pintype "passive"))
      (node (ref "C12") (pin "1") (pinfunction "1_1") (pintype "passive"))
      (node (ref "C15") (pin "1") (pinfunction "1_1") (pintype "passive"))
      (node (ref "C16") (pin "1") (pinfunction "1_1") (pintype "passive"))
      (node (ref "C28") (pin "1") (pinfunction "1_1") (pintype "passive"))
      (node (ref "C29") (pin "1") (pinfunction "1_1") (pintype "passive"))
      (node (ref "C30") (pin "1") (pinfunction "1_1") (pintype "passive"))
      (node (ref "C31") (pin "1") (pinfunction "1_1") (pintype "passive"))
      (node (ref "C32") (pin "1") (pinfunction "1_1") (pintype "passive"))
      (node (ref "C33") (pin "1") (pinfunction "1_1") (pintype "passive"))
      (node (ref "C34") (pin "1") (pinfunction "1_1") (pintype "passive"))
      (node (ref "C37") (pin "1") (pinfunction "1_1") (pintype "passive"))
      (node (ref "C38") (pin "1") (pinfunction "1_1") (pintype "passive"))
      (node (ref "C39") (pin "1") (pinfunction "1_1") (pintype "passive"))
      (node (ref "C40") (pin "1") (pinfunction "1_1") (pintype "passive"))
      (node (ref "C41") (pin "1") (pinfunction "1_1") (pintype "passive"))
      (node (ref "C42") (pin "1") (pinfunction "1_1") (pintype "passive"))
      (node (ref "C43") (pin "1") (pinfunction "1_1") (pintype "passive"))
      (node (ref "C49") (pin "1") (pinfunction "1_1") (pintype "passive"))
      (node (ref "C50") (pin "1") (pinfunction "1_1") (pintype "passive"))
      (node (ref "C51") (pin "1") (pinfunction "1_1") (pintype "passive"))
      (node (ref "C52") (pin "1") (pinfunction "1_1") (pintype "passive"))
      (node (ref "C53") (pin "1") (pinfunction "1_1") (pintype "passive"))
      (node (ref "C54") (pin "1") (pinfunction "1_1") (pintype "passive"))
      (node (ref "C55") (pin "1") (pinfunction "1_1") (pintype "passive"))
      (node (ref "C56") (pin "1") (pinfunction "1_1") (pintype "passive"))
      (node (ref "C57") (pin "1") (pinfunction "1_1") (pintype "passive"))
      (node (ref "C58") (pin "1") (pinfunction "1_1") (pintype "passive"))
      (node (ref "C59") (pin "1") (pinfunction "1_1") (pintype "passive"))
      (node (ref "C60") (pin "1") (pinfunction "1_1") (pintype "passive"))
      (node (ref "C61") (pin "1") (pinfunction "1_1") (pintype "passive"))
      (node (ref "C62") (pin "1") (pinfunction "1_1") (pintype "passive"))
      (node (ref "C63") (pin "1") (pinfunction "1_1") (pintype "passive"))
      (node (ref "C67") (pin "+") (pinfunction "+_+") (pintype "passive"))
      (node (ref "C69") (pin "1") (pinfunction "1_1") (pintype "passive"))
      (node (ref "C7") (pin "1") (pinfunction "1_1") (pintype "passive"))
      (node (ref "C8") (pin "1") (pinfunction "1_1") (pintype "passive"))
      (node (ref "C9") (pin "1") (pinfunction "1_1") (pintype "passive"))
      (node (ref "FB1") (pin "1") (pinfunction "P$1_1") (pintype "passive"))
      (node (ref "FB2") (pin "1") (pinfunction "P$1_1") (pintype "passive"))
      (node (ref "IC1") (pin "22") (pinfunction "~{FORCEOFF}_22") (pintype "input"))
      (node (ref "IC1") (pin "23") (pinfunction "FORCEON_23") (pintype "input"))
      (node (ref "IC1") (pin "26") (pinfunction "VCC_26") (pintype "power_in"))
      (node (ref "IC11") (pin "4") (pinfunction "VOUT_4") (pintype "bidirectional"))
      (node (ref "IC2") (pin "10") (pinfunction "3V3OUT_10") (pintype "bidirectional"))
      (node (ref "IC2") (pin "11") (pinfunction "RESET#_11") (pintype "bidirectional"))
      (node (ref "IC2") (pin "12") (pinfunction "VCC_12") (pintype "bidirectional"))
      (node (ref "IC2") (pin "3") (pinfunction "VCCIO_3") (pintype "bidirectional"))
      (node (ref "IC3") (pin "15") (pinfunction "VDDTX_15") (pintype "input"))
      (node (ref "IC3") (pin "19") (pinfunction "VDDRX_19") (pintype "input"))
      (node (ref "IC3") (pin "20") (pinfunction "VDDPLL_20") (pintype "input"))
      (node (ref "IC3") (pin "25") (pinfunction "VDDOSC_25") (pintype "input"))
      (node (ref "IC3") (pin "28") (pinfunction "VDD_28") (pintype "input"))
      (node (ref "IC4") (pin "20") (pinfunction "DVDD_20") (pintype "bidirectional"))
      (node (ref "IC5") (pin "1") (pinfunction "VDD0_1") (pintype "power_in"))
      (node (ref "IC5") (pin "14") (pinfunction "VDD1_14") (pintype "power_in"))
      (node (ref "IC5") (pin "27") (pinfunction "VDD2_27") (pintype "power_in"))
      (node (ref "IC5") (pin "3") (pinfunction "VDDQ0_3") (pintype "power_in"))
      (node (ref "IC5") (pin "37") (pinfunction "CKE_37") (pintype "input"))
      (node (ref "IC5") (pin "43") (pinfunction "VDDQ2_43") (pintype "power_in"))
      (node (ref "IC5") (pin "49") (pinfunction "VDDQ3_49") (pintype "power_in"))
      (node (ref "IC5") (pin "9") (pinfunction "VDDQ1_9") (pintype "power_in"))
      (node (ref "IC6") (pin "8") (pinfunction "VCC_8") (pintype "bidirectional"))
      (node (ref "IC7") (pin "8") (pinfunction "VCC_8") (pintype "bidirectional"))
      (node (ref "IC8") (pin "7") (pinfunction "#HOLD_7") (pintype "bidirectional"))
      (node (ref "IC8") (pin "8") (pinfunction "VCC_8") (pintype "bidirectional"))
      (node (ref "IC9") (pin "1") (pinfunction "VCC_ONE10_1") (pintype "bidirectional"))
      (node (ref "IC9") (pin "103") (pinfunction "VCCIO6_2_103") (pintype "bidirectional"))
      (node (ref "IC9") (pin "108") (pinfunction "VCC_ONE9_108") (pintype "bidirectional"))
      (node (ref "IC9") (pin "109") (pinfunction "VCC_ONE8_109") (pintype "bidirectional"))
      (node (ref "IC9") (pin "115") (pinfunction "VCC_ONE7_115") (pintype "bidirectional"))
      (node (ref "IC9") (pin "117") (pinfunction "VCCIO7_117") (pintype "bidirectional"))
      (node (ref "IC9") (pin "128") (pinfunction "VCCIO8_2_128") (pintype "bidirectional"))
      (node (ref "IC9") (pin "139") (pinfunction "VCCIO8_1_139") (pintype "bidirectional"))
      (node (ref "IC9") (pin "144") (pinfunction "VCC_ONE6_144") (pintype "bidirectional"))
      (node (ref "IC9") (pin "23") (pinfunction "VCCIO1B_23") (pintype "bidirectional"))
      (node (ref "IC9") (pin "31") (pinfunction "VCCIO2_31") (pintype "bidirectional"))
      (node (ref "IC9") (pin "36") (pinfunction "VCC_ONE5_36") (pintype "bidirectional"))
      (node (ref "IC9") (pin "37") (pinfunction "VCC_ONE4_37") (pintype "bidirectional"))
      (node (ref "IC9") (pin "40") (pinfunction "VCCIO3_1_40") (pintype "bidirectional"))
      (node (ref "IC9") (pin "49") (pinfunction "VCCIO3_2_49") (pintype "bidirectional"))
      (node (ref "IC9") (pin "51") (pinfunction "VCC_ONE3_51") (pintype "bidirectional"))
      (node (ref "IC9") (pin "67") (pinfunction "VCCIO4_67") (pintype "bidirectional"))
      (node (ref "IC9") (pin "72") (pinfunction "VCC_ONE1_72") (pintype "bidirectional"))
      (node (ref "IC9") (pin "73") (pinfunction "VCC_ONE2_73") (pintype "bidirectional"))
      (node (ref "IC9") (pin "82") (pinfunction "VCCIO5_82") (pintype "bidirectional"))
      (node (ref "IC9") (pin "9") (pinfunction "VCCIO1A_9") (pintype "bidirectional"))
      (node (ref "IC9") (pin "94") (pinfunction "VCCIO6_1_94") (pintype "bidirectional"))
      (node (ref "LED2") (pin "A") (pinfunction "A_A") (pintype "passive"))
      (node (ref "LED3") (pin "A") (pinfunction "A_A") (pintype "passive"))
      (node (ref "Q4") (pin "1") (pinfunction "CON_1") (pintype "input"))
      (node (ref "Q4") (pin "4") (pinfunction "VDD_4") (pintype "power_in"))
      (node (ref "Q5") (pin "1") (pinfunction "CON_1") (pintype "input"))
      (node (ref "Q5") (pin "4") (pinfunction "VDD_4") (pintype "power_in"))
      (node (ref "Q6") (pin "1") (pinfunction "CON_1") (pintype "input"))
      (node (ref "Q6") (pin "4") (pinfunction "VDD_4") (pintype "power_in"))
      (node (ref "R33") (pin "1") (pinfunction "1_1") (pintype "passive"))
      (node (ref "R34") (pin "1") (pinfunction "1_1") (pintype "passive"))
      (node (ref "R36") (pin "2") (pinfunction "2_2") (pintype "passive"))
      (node (ref "R37") (pin "2") (pinfunction "2_2") (pintype "passive"))
      (node (ref "R41") (pin "2") (pinfunction "2_2") (pintype "passive"))
      (node (ref "R42") (pin "2") (pinfunction "2_2") (pintype "passive"))
      (node (ref "R43") (pin "2") (pinfunction "2_2") (pintype "passive"))
      (node (ref "R48") (pin "2") (pinfunction "2_2") (pintype "passive"))
      (node (ref "R5") (pin "1") (pinfunction "1_1") (pintype "passive"))
      (node (ref "SJ1") (pin "1") (pinfunction "1_1") (pintype "passive"))
      (node (ref "SJ2") (pin "1") (pinfunction "1_1") (pintype "passive"))
      (node (ref "SJ3") (pin "1") (pinfunction "1_1") (pintype "passive"))
      (node (ref "SJ4") (pin "1") (pinfunction "1_1") (pintype "passive"))
      (node (ref "SJ5") (pin "1") (pinfunction "1_1") (pintype "passive"))
      (node (ref "SJ6") (pin "1") (pinfunction "1_1") (pintype "passive"))
      (node (ref "X10") (pin "1") (pinfunction "1_1") (pintype "bidirectional"))
      (node (ref "X11") (pin "4") (pinfunction "KL_4") (pintype "passive"))
      (node (ref "X7") (pin "VDD") (pinfunction "VDD_VDD") (pintype "bidirectional"))
      (node (ref "X9") (pin "6") (pinfunction "KL_6") (pintype "passive"))
    )
    (net (code "2") (name "+3V3_A") (class "Default")
      (node (ref "C14") (pin "1") (pinfunction "1_1") (pintype "passive"))
      (node (ref "C18") (pin "1") (pinfunction "1_1") (pintype "passive"))
      (node (ref "C23") (pin "1") (pinfunction "1_1") (pintype "passive"))
      (node (ref "FB1") (pin "2") (pinfunction "P$2_2") (pintype "passive"))
      (node (ref "IC4") (pin "1") (pinfunction "CPVDD_1") (pintype "bidirectional"))
      (node (ref "IC4") (pin "8") (pinfunction "AVDD_8") (pintype "bidirectional"))
    )
    (net (code "3") (name "+3V3_SB") (class "Default")
      (node (ref "C65") (pin "1") (pinfunction "1_1") (pintype "passive"))
      (node (ref "C70") (pin "+") (pinfunction "+_+") (pintype "passive"))
      (node (ref "C71") (pin "1") (pinfunction "1_1") (pintype "passive"))
      (node (ref "IC12") (pin "18") (pinfunction "AVCC_18") (pintype "power_in"))
      (node (ref "IC12") (pin "4") (pinfunction "VCC_4") (pintype "power_in"))
      (node (ref "IC13") (pin "2") (pinfunction "VOUT_2") (pintype "bidirectional"))
      (node (ref "IC13") (pin "4") (pinfunction "P_4") (pintype "bidirectional"))
      (node (ref "R32") (pin "2") (pinfunction "2_2") (pintype "passive"))
      (node (ref "R49") (pin "2") (pinfunction "2_2") (pintype "passive"))
      (node (ref "X13") (pin "2") (pinfunction "2_2") (pintype "bidirectional"))
    )
    (net (code "4") (name "+5V") (class "Default")
      (node (ref "C10") (pin "1") (pinfunction "1_1") (pintype "passive"))
      (node (ref "C66") (pin "+") (pinfunction "+_+") (pintype "passive"))
      (node (ref "C68") (pin "1") (pinfunction "1_1") (pintype "passive"))
      (node (ref "IC10") (pin "4") (pinfunction "VOUT_4") (pintype "bidirectional"))
      (node (ref "IC11") (pin "1") (pinfunction "EN_1") (pintype "bidirectional"))
      (node (ref "IC11") (pin "2") (pinfunction "VIN_2") (pintype "bidirectional"))
      (node (ref "Q3") (pin "P") (pinfunction "P_P") (pintype "bidirectional"))
      (node (ref "R19") (pin "2") (pinfunction "2_2") (pintype "passive"))
      (node (ref "R20") (pin "2") (pinfunction "2_2") (pintype "passive"))
      (node (ref "R21") (pin "2") (pinfunction "2_2") (pintype "passive"))
      (node (ref "R22") (pin "2") (pinfunction "2_2") (pintype "passive"))
      (node (ref "R47") (pin "2") (pinfunction "2_2") (pintype "passive"))
      (node (ref "X4") (pin "4") (pinfunction "5_4") (pintype "bidirectional"))
      (node (ref "X9") (pin "2") (pinfunction "KL_2") (pintype "passive"))
    )
    (net (code "5") (name "AUDIO_MUTE") (class "Default")
      (node (ref "IC12") (pin "28") (pinfunction "PC5(ADC5/SCL/PCINT13)_28") (pintype "bidirectional"))
      (node (ref "IC4") (pin "17") (pinfunction "XSMT_17") (pintype "input"))
    )
    (net (code "6") (name "CLK_18M432") (class "Default")
      (node (ref "IC9") (pin "91") (pinfunction "PIN91_91") (pintype "bidirectional"))
      (node (ref "Q5") (pin "3") (pinfunction "OUT_3") (pintype "output"))
    )
    (net (code "7") (name "CLK_22M5792") (class "Default")
      (node (ref "IC9") (pin "90") (pinfunction "PIN90_90") (pintype "bidirectional"))
      (node (ref "Q6") (pin "3") (pinfunction "OUT_3") (pintype "output"))
    )
    (net (code "8") (name "CLK_25M") (class "Default")
      (node (ref "IC9") (pin "26") (pinfunction "PIN26_26") (pintype "bidirectional"))
      (node (ref "Q4") (pin "3") (pinfunction "OUT_3") (pintype "output"))
    )
    (net (code "9") (name "CONF_DONE") (class "Default")
      (node (ref "IC9") (pin "138") (pinfunction "PIN138_138") (pintype "bidirectional"))
      (node (ref "R42") (pin "1") (pinfunction "1_1") (pintype "passive"))
    )
    (net (code "10") (name "CONF_SEL") (class "Default")
      (node (ref "IC9") (pin "126") (pinfunction "PIN126_126") (pintype "bidirectional"))
      (node (ref "R44") (pin "1") (pinfunction "1_1") (pintype "passive"))
    )
    (net (code "11") (name "CPU_LED") (class "Default")
      (node (ref "IC12") (pin "9") (pinfunction "PD5(PCINT21/OC0B/T1)_9") (pintype "bidirectional"))
      (node (ref "R39") (pin "2") (pinfunction "2_2") (pintype "passive"))
      (node (ref "X10") (pin "3") (pinfunction "3_3") (pintype "bidirectional"))
    )
    (net (code "12") (name "CTS1") (class "Default")
      (node (ref "IC1") (pin "7") (pinfunction "R4IN_7") (pintype "input"))
      (node (ref "X2") (pin "8") (pinfunction "8_8") (pintype "passive"))
    )
    (net (code "13") (name "DCD1") (class "Default")
      (node (ref "IC1") (pin "4") (pinfunction "R1IN_4") (pintype "input"))
      (node (ref "X2") (pin "1") (pinfunction "1_1") (pintype "passive"))
    )
    (net (code "14") (name "DEMP") (class "Default")
      (node (ref "IC4") (pin "10") (pinfunction "DEMP_10") (pintype "input"))
      (node (ref "SJ3") (pin "2") (pinfunction "2_2") (pintype "passive"))
    )
    (net (code "15") (name "DSR1") (class "Default")
      (node (ref "IC1") (pin "5") (pinfunction "R2IN_5") (pintype "input"))
      (node (ref "X2") (pin "6") (pinfunction "6_6") (pintype "passive"))
    )
    (net (code "16") (name "DTR1") (class "Default")
      (node (ref "IC1") (pin "11") (pinfunction "T3OUT_11") (pintype "output"))
      (node (ref "X2") (pin "4") (pinfunction "4_4") (pintype "passive"))
    )
    (net (code "17") (name "ENC_CS") (class "Default")
      (node (ref "IC3") (pin "9") (pinfunction "~{CS}_9") (pintype "input"))
      (node (ref "IC9") (pin "21") (pinfunction "PIN21_21") (pintype "bidirectional"))
    )
    (net (code "18") (name "ENC_INT") (class "Default")
      (node (ref "IC3") (pin "4") (pinfunction "~{INT}_4") (pintype "output"))
      (node (ref "IC9") (pin "27") (pinfunction "PIN27_27") (pintype "bidirectional"))
    )
    (net (code "19") (name "ENC_SCK") (class "Default")
      (node (ref "IC3") (pin "8") (pinfunction "SCK_8") (pintype "input"))
      (node (ref "IC9") (pin "22") (pinfunction "PIN22_22") (pintype "bidirectional"))
    )
    (net (code "20") (name "ENC_SI") (class "Default")
      (node (ref "IC3") (pin "7") (pinfunction "SI_7") (pintype "input"))
      (node (ref "IC9") (pin "24") (pinfunction "PIN24_24") (pintype "bidirectional"))
    )
    (net (code "21") (name "ENC_SO") (class "Default")
      (node (ref "IC3") (pin "6") (pinfunction "SO_6") (pintype "output"))
      (node (ref "IC9") (pin "25") (pinfunction "PIN25_25") (pintype "bidirectional"))
    )
    (net (code "22") (name "EX_CMD0") (class "Default")
      (node (ref "IC9") (pin "99") (pinfunction "PIN99_99") (pintype "bidirectional"))
      (node (ref "X9") (pin "1") (pinfunction "KL_1") (pintype "passive"))
    )
    (net (code "23") (name "EX_CMD1") (class "Default")
      (node (ref "IC9") (pin "98") (pinfunction "PIN98_98") (pintype "bidirectional"))
      (node (ref "X9") (pin "3") (pinfunction "KL_3") (pintype "passive"))
    )
    (net (code "24") (name "EX_CMD2") (class "Default")
      (node (ref "IC9") (pin "92") (pinfunction "PIN92_92") (pintype "bidirectional"))
      (node (ref "X9") (pin "11") (pinfunction "KL_11") (pintype "passive"))
    )
    (net (code "25") (name "EX_CMD3") (class "Default")
      (node (ref "IC9") (pin "87") (pinfunction "PIN87_87") (pintype "bidirectional"))
      (node (ref "X9") (pin "15") (pinfunction "KL_15") (pintype "passive"))
    )
    (net (code "26") (name "EX_DQ0") (class "Default")
      (node (ref "IC9") (pin "84") (pinfunction "PIN84_84") (pintype "bidirectional"))
      (node (ref "X9") (pin "19") (pinfunction "KL_19") (pintype "passive"))
    )
    (net (code "27") (name "EX_DQ1") (class "Default")
      (node (ref "IC9") (pin "85") (pinfunction "PIN85_85") (pintype "bidirectional"))
      (node (ref "X9") (pin "17") (pinfunction "KL_17") (pintype "passive"))
    )
    (net (code "28") (name "EX_DQ2") (class "Default")
      (node (ref "IC9") (pin "86") (pinfunction "PIN86_86") (pintype "bidirectional"))
      (node (ref "X9") (pin "16") (pinfunction "KL_16") (pintype "passive"))
    )
    (net (code "29") (name "EX_DQ3") (class "Default")
      (node (ref "IC9") (pin "88") (pinfunction "PIN88_88") (pintype "bidirectional"))
      (node (ref "X9") (pin "14") (pinfunction "KL_14") (pintype "passive"))
    )
    (net (code "30") (name "EX_DQ4") (class "Default")
      (node (ref "IC9") (pin "89") (pinfunction "PIN89_89") (pintype "bidirectional"))
      (node (ref "X9") (pin "12") (pinfunction "KL_12") (pintype "passive"))
    )
    (net (code "31") (name "EX_DQ5") (class "Default")
      (node (ref "IC9") (pin "93") (pinfunction "PIN93_93") (pintype "bidirectional"))
      (node (ref "X9") (pin "10") (pinfunction "KL_10") (pintype "passive"))
    )
    (net (code "32") (name "EX_DQ6") (class "Default")
      (node (ref "IC9") (pin "96") (pinfunction "PIN96_96") (pintype "bidirectional"))
      (node (ref "X9") (pin "8") (pinfunction "KL_8") (pintype "passive"))
    )
    (net (code "33") (name "EX_DQ7") (class "Default")
      (node (ref "IC9") (pin "97") (pinfunction "PIN97_97") (pintype "bidirectional"))
      (node (ref "X9") (pin "5") (pinfunction "KL_5") (pintype "passive"))
    )
    (net (code "34") (name "FILTER") (class "Default")
      (node (ref "IC4") (pin "11") (pinfunction "FLT_11") (pintype "input"))
      (node (ref "SJ1") (pin "2") (pinfunction "2_2") (pintype "passive"))
    )
    (net (code "35") (name "FLASH_CS") (class "Default")
      (node (ref "IC8") (pin "1") (pinfunction "#CS_1") (pintype "bidirectional"))
      (node (ref "IC9") (pin "13") (pinfunction "PIN13_13") (pintype "bidirectional"))
    )
    (net (code "36") (name "FLASH_SCK") (class "Default")
      (node (ref "IC8") (pin "6") (pinfunction "SCK_6") (pintype "bidirectional"))
      (node (ref "IC9") (pin "17") (pinfunction "PIN17_17") (pintype "bidirectional"))
    )
    (net (code "37") (name "FLASH_SI") (class "Default")
      (node (ref "IC8") (pin "5") (pinfunction "SI_5") (pintype "bidirectional"))
      (node (ref "IC9") (pin "15") (pinfunction "PIN15_15") (pintype "bidirectional"))
    )
    (net (code "38") (name "FLASH_SO") (class "Default")
      (node (ref "IC8") (pin "2") (pinfunction "SO_2") (pintype "bidirectional"))
      (node (ref "IC9") (pin "14") (pinfunction "PIN14_14") (pintype "bidirectional"))
    )
    (net (code "39") (name "FORMAT") (class "Default")
      (node (ref "IC4") (pin "16") (pinfunction "FMT_16") (pintype "input"))
      (node (ref "SJ2") (pin "2") (pinfunction "2_2") (pintype "passive"))
    )
    (net (code "40") (name "GND") (class "Default")
      (node (ref "C10") (pin "2") (pinfunction "2_2") (pintype "passive"))
      (node (ref "C11") (pin "2") (pinfunction "2_2") (pintype "passive"))
      (node (ref "C12") (pin "2") (pinfunction "2_2") (pintype "passive"))
      (node (ref "C13") (pin "1") (pinfunction "1_1") (pintype "passive"))
      (node (ref "C14") (pin "2") (pinfunction "2_2") (pintype "passive"))
      (node (ref "C15") (pin "2") (pinfunction "2_2") (pintype "passive"))
      (node (ref "C16") (pin "2") (pinfunction "2_2") (pintype "passive"))
      (node (ref "C17") (pin "2") (pinfunction "2_2") (pintype "passive"))
      (node (ref "C18") (pin "2") (pinfunction "2_2") (pintype "passive"))
      (node (ref "C19") (pin "1") (pinfunction "1_1") (pintype "passive"))
      (node (ref "C21") (pin "2") (pinfunction "2_2") (pintype "passive"))
      (node (ref "C22") (pin "2") (pinfunction "2_2") (pintype "passive"))
      (node (ref "C23") (pin "2") (pinfunction "2_2") (pintype "passive"))
      (node (ref "C24") (pin "2") (pinfunction "2_2") (pintype "passive"))
      (node (ref "C25") (pin "2") (pinfunction "2_2") (pintype "passive"))
      (node (ref "C26") (pin "2") (pinfunction "2_2") (pintype "passive"))
      (node (ref "C27") (pin "2") (pinfunction "2_2") (pintype "passive"))
      (node (ref "C28") (pin "2") (pinfunction "2_2") (pintype "passive"))
      (node (ref "C29") (pin "2") (pinfunction "2_2") (pintype "passive"))
      (node (ref "C3") (pin "2") (pinfunction "2_2") (pintype "passive"))
      (node (ref "C30") (pin "2") (pinfunction "2_2") (pintype "passive"))
      (node (ref "C31") (pin "2") (pinfunction "2_2") (pintype "passive"))
      (node (ref "C32") (pin "2") (pinfunction "2_2") (pintype "passive"))
      (node (ref "C33") (pin "2") (pinfunction "2_2") (pintype "passive"))
      (node (ref "C34") (pin "2") (pinfunction "2_2") (pintype "passive"))
      (node (ref "C35") (pin "2") (pinfunction "2_2") (pintype "passive"))
      (node (ref "C36") (pin "2") (pinfunction "2_2") (pintype "passive"))
      (node (ref "C37") (pin "2") (pinfunction "2_2") (pintype "passive"))
      (node (ref "C38") (pin "2") (pinfunction "2_2") (pintype "passive"))
      (node (ref "C39") (pin "2") (pinfunction "2_2") (pintype "passive"))
      (node (ref "C4") (pin "2") (pinfunction "2_2") (pintype "passive"))
      (node (ref "C40") (pin "2") (pinfunction "2_2") (pintype "passive"))
      (node (ref "C41") (pin "2") (pinfunction "2_2") (pintype "passive"))
      (node (ref "C42") (pin "2") (pinfunction "2_2") (pintype "passive"))
      (node (ref "C43") (pin "2") (pinfunction "2_2") (pintype "passive"))
      (node (ref "C44") (pin "2") (pinfunction "2_2") (pintype "passive"))
      (node (ref "C45") (pin "2") (pinfunction "2_2") (pintype "passive"))
      (node (ref "C46") (pin "2") (pinfunction "2_2") (pintype "passive"))
      (node (ref "C47") (pin "2") (pinfunction "2_2") (pintype "passive"))
      (node (ref "C48") (pin "2") (pinfunction "2_2") (pintype "passive"))
      (node (ref "C49") (pin "2") (pinfunction "2_2") (pintype "passive"))
      (node (ref "C5") (pin "2") (pinfunction "2_2") (pintype "passive"))
      (node (ref "C50") (pin "2") (pinfunction "2_2") (pintype "passive"))
      (node (ref "C51") (pin "2") (pinfunction "2_2") (pintype "passive"))
      (node (ref "C52") (pin "2") (pinfunction "2_2") (pintype "passive"))
      (node (ref "C53") (pin "2") (pinfunction "2_2") (pintype "passive"))
      (node (ref "C54") (pin "2") (pinfunction "2_2") (pintype "passive"))
      (node (ref "C55") (pin "2") (pinfunction "2_2") (pintype "passive"))
      (node (ref "C56") (pin "2") (pinfunction "2_2") (pintype "passive"))
      (node (ref "C57") (pin "2") (pinfunction "2_2") (pintype "passive"))
      (node (ref "C58") (pin "2") (pinfunction "2_2") (pintype "passive"))
      (node (ref "C59") (pin "2") (pinfunction "2_2") (pintype "passive"))
      (node (ref "C6") (pin "2") (pinfunction "2_2") (pintype "passive"))
      (node (ref "C60") (pin "2") (pinfunction "2_2") (pintype "passive"))
      (node (ref "C61") (pin "2") (pinfunction "2_2") (pintype "passive"))
      (node (ref "C62") (pin "2") (pinfunction "2_2") (pintype "passive"))
      (node (ref "C63") (pin "2") (pinfunction "2_2") (pintype "passive"))
      (node (ref "C64") (pin "-") (pinfunction "-_-") (pintype "passive"))
      (node (ref "C65") (pin "2") (pinfunction "2_2") (pintype "passive"))
      (node (ref "C66") (pin "-") (pinfunction "-_-") (pintype "passive"))
      (node (ref "C67") (pin "-") (pinfunction "-_-") (pintype "passive"))
      (node (ref "C68") (pin "2") (pinfunction "2_2") (pintype "passive"))
      (node (ref "C69") (pin "2") (pinfunction "2_2") (pintype "passive"))
      (node (ref "C7") (pin "2") (pinfunction "2_2") (pintype "passive"))
      (node (ref "C70") (pin "-") (pinfunction "-_-") (pintype "passive"))
      (node (ref "C71") (pin "2") (pinfunction "2_2") (pintype "passive"))
      (node (ref "C8") (pin "2") (pinfunction "2_2") (pintype "passive"))
      (node (ref "C9") (pin "2") (pinfunction "2_2") (pintype "passive"))
      (node (ref "IC1") (pin "25") (pinfunction "GND_25") (pintype "power_in"))
      (node (ref "IC10") (pin "3") (pinfunction "GND_3") (pintype "bidirectional"))
      (node (ref "IC10") (pin "P") (pinfunction "P_P") (pintype "bidirectional"))
      (node (ref "IC11") (pin "3") (pinfunction "GND_3") (pintype "bidirectional"))
      (node (ref "IC11") (pin "P") (pinfunction "P_P") (pintype "bidirectional"))
      (node (ref "IC12") (pin "21") (pinfunction "GND_21") (pintype "power_in"))
      (node (ref "IC12") (pin "5") (pinfunction "GND_5") (pintype "power_in"))
      (node (ref "IC13") (pin "1") (pinfunction "GND_1") (pintype "bidirectional"))
      (node (ref "IC2") (pin "13") (pinfunction "GND_1_13") (pintype "bidirectional"))
      (node (ref "IC2") (pin "5") (pinfunction "GND_5") (pintype "bidirectional"))
      (node (ref "IC3") (pin "11") (pinfunction "VSSRX_11") (pintype "input"))
      (node (ref "IC3") (pin "18") (pinfunction "VSSTX_18") (pintype "input"))
      (node (ref "IC3") (pin "2") (pinfunction "VSS_2") (pintype "input"))
      (node (ref "IC3") (pin "21") (pinfunction "VSSPLL_21") (pintype "input"))
      (node (ref "IC3") (pin "22") (pinfunction "VSSOSC_22") (pintype "input"))
      (node (ref "IC4") (pin "12") (pinfunction "SCK_12") (pintype "input"))
      (node (ref "IC4") (pin "19") (pinfunction "DGND_19") (pintype "bidirectional"))
      (node (ref "IC4") (pin "3") (pinfunction "CPGND_3") (pintype "bidirectional"))
      (node (ref "IC4") (pin "9") (pinfunction "AGND_9") (pintype "bidirectional"))
      (node (ref "IC5") (pin "12") (pinfunction "VSSQ1_12") (pintype "power_in"))
      (node (ref "IC5") (pin "19") (pinfunction "CS#_19") (pintype "input"))
      (node (ref "IC5") (pin "28") (pinfunction "VSS0_28") (pintype "power_in"))
      (node (ref "IC5") (pin "39") (pinfunction "DQM_39") (pintype "input"))
      (node (ref "IC5") (pin "41") (pinfunction "VSS1_41") (pintype "power_in"))
      (node (ref "IC5") (pin "46") (pinfunction "VSSQ2_46") (pintype "power_in"))
      (node (ref "IC5") (pin "52") (pinfunction "VSSQ3_52") (pintype "power_in"))
      (node (ref "IC5") (pin "54") (pinfunction "VSS2_54") (pintype "power_in"))
      (node (ref "IC5") (pin "6") (pinfunction "VSSQ0_6") (pintype "power_in"))
      (node (ref "IC6") (pin "4") (pinfunction "VSS_4") (pintype "bidirectional"))
      (node (ref "IC7") (pin "4") (pinfunction "VSS_4") (pintype "bidirectional"))
      (node (ref "IC8") (pin "4") (pinfunction "GND_4") (pintype "bidirectional"))
      (node (ref "IC9") (pin "104") (pinfunction "GND12_104") (pintype "bidirectional"))
      (node (ref "IC9") (pin "116") (pinfunction "GND11_116") (pintype "bidirectional"))
      (node (ref "IC9") (pin "125") (pinfunction "GND10_125") (pintype "bidirectional"))
      (node (ref "IC9") (pin "133") (pinfunction "GND9_133") (pintype "bidirectional"))
      (node (ref "IC9") (pin "137") (pinfunction "GND8_137") (pintype "bidirectional"))
      (node (ref "IC9") (pin "142") (pinfunction "GND7_142") (pintype "bidirectional"))
      (node (ref "IC9") (pin "3") (pinfunction "ANAIN1_3") (pintype "bidirectional"))
      (node (ref "IC9") (pin "4") (pinfunction "REF_GND_4") (pintype "bidirectional"))
      (node (ref "IC9") (pin "42") (pinfunction "GND6_42") (pintype "bidirectional"))
      (node (ref "IC9") (pin "53") (pinfunction "GND5_53") (pintype "bidirectional"))
      (node (ref "IC9") (pin "63") (pinfunction "GND4_63") (pintype "bidirectional"))
      (node (ref "IC9") (pin "68") (pinfunction "GND3_68") (pintype "bidirectional"))
      (node (ref "IC9") (pin "83") (pinfunction "GND2_83") (pintype "bidirectional"))
      (node (ref "IC9") (pin "95") (pinfunction "GND1_95") (pintype "bidirectional"))
      (node (ref "IC9") (pin "E") (pinfunction "EGND_E") (pintype "bidirectional"))
      (node (ref "Q1") (pin "2") (pinfunction "2_2") (pintype "passive"))
      (node (ref "Q1") (pin "4") (pinfunction "4_4") (pintype "passive"))
      (node (ref "Q4") (pin "2") (pinfunction "VSS_2") (pintype "power_in"))
      (node (ref "Q5") (pin "2") (pinfunction "VSS_2") (pintype "power_in"))
      (node (ref "Q6") (pin "2") (pinfunction "VSS_2") (pintype "power_in"))
      (node (ref "R23") (pin "2") (pinfunction "2_2") (pintype "passive"))
      (node (ref "R38") (pin "2") (pinfunction "2_2") (pintype "passive"))
      (node (ref "R4") (pin "1") (pinfunction "1_1") (pintype "passive"))
      (node (ref "R40") (pin "2") (pinfunction "2_2") (pintype "passive"))
      (node (ref "R45") (pin "1") (pinfunction "1_1") (pintype "passive"))
      (node (ref "R46") (pin "1") (pinfunction "1_1") (pintype "passive"))
      (node (ref "R51") (pin "1") (pinfunction "1_1") (pintype "passive"))
      (node (ref "S1") (pin "3") (pinfunction "3_3") (pintype "passive"))
      (node (ref "S1") (pin "4") (pinfunction "4_4") (pintype "passive"))
      (node (ref "S2") (pin "3") (pinfunction "3_3") (pintype "passive"))
      (node (ref "S2") (pin "4") (pinfunction "4_4") (pintype "passive"))
      (node (ref "SJ1") (pin "3") (pinfunction "3_3") (pintype "passive"))
      (node (ref "SJ2") (pin "3") (pinfunction "3_3") (pintype "passive"))
      (node (ref "SJ3") (pin "3") (pinfunction "3_3") (pintype "passive"))
      (node (ref "SJ4") (pin "3") (pinfunction "3_3") (pintype "passive"))
      (node (ref "SJ5") (pin "3") (pinfunction "3_3") (pintype "passive"))
      (node (ref "SJ6") (pin "3") (pinfunction "3_3") (pintype "passive"))
      (node (ref "T1") (pin "1") (pinfunction "E_1") (pintype "passive"))
      (node (ref "X1") (pin "5") (pinfunction "5_5") (pintype "input"))
      (node (ref "X1") (pin "M1") (pinfunction "GND1_M1") (pintype "bidirectional"))
      (node (ref "X1") (pin "M2") (pinfunction "GND2_M2") (pintype "bidirectional"))
      (node (ref "X1") (pin "M3") (pinfunction "GND3_M3") (pintype "bidirectional"))
      (node (ref "X1") (pin "M4") (pinfunction "GND4_M4") (pintype "bidirectional"))
      (node (ref "X10") (pin "6") (pinfunction "6_6") (pintype "bidirectional"))
      (node (ref "X11") (pin "10") (pinfunction "KL_10") (pintype "passive"))
      (node (ref "X11") (pin "2") (pinfunction "KL_2") (pintype "passive"))
      (node (ref "X12") (pin "2") (pinfunction "1_2") (pintype "passive"))
      (node (ref "X12") (pin "3") (pinfunction "2_3") (pintype "passive"))
      (node (ref "X13") (pin "6") (pinfunction "6_6") (pintype "bidirectional"))
      (node (ref "X2") (pin "5") (pinfunction "5_5") (pintype "passive"))
      (node (ref "X2") (pin "G1") (pinfunction "G1_G1") (pintype "passive"))
      (node (ref "X2") (pin "G2") (pinfunction "G2_G2") (pintype "passive"))
      (node (ref "X3") (pin "10") (pinfunction "10_10") (pintype "passive"))
      (node (ref "X3") (pin "5") (pinfunction "5_5") (pintype "passive"))
      (node (ref "X3") (pin "6") (pinfunction "6_6") (pintype "passive"))
      (node (ref "X3") (pin "7") (pinfunction "7_7") (pintype "passive"))
      (node (ref "X3") (pin "8") (pinfunction "8_8") (pintype "passive"))
      (node (ref "X3") (pin "SCH1") (pinfunction "P$1_SCH1") (pintype "passive"))
      (node (ref "X3") (pin "SCH2") (pinfunction "P$2_SCH2") (pintype "passive"))
      (node (ref "X4") (pin "3") (pinfunction "6_3") (pintype "bidirectional"))
      (node (ref "X4") (pin "CASE1") (pinfunction "CASE1_CASE1") (pintype "bidirectional"))
      (node (ref "X4") (pin "CASE2") (pinfunction "CASE2_CASE2") (pintype "bidirectional"))
      (node (ref "X4") (pin "SHIELDING") (pinfunction "SHIELDING_SHIELDING") (pintype "bidirectional"))
      (node (ref "X5") (pin "GND1") (pinfunction "GND1_GND1") (pintype "power_in"))
      (node (ref "X5") (pin "GND2") (pinfunction "GND2_GND2") (pintype "power_in"))
      (node (ref "X5") (pin "LEDG_K") (pinfunction "LEDG-_LEDG_K") (pintype "bidirectional"))
      (node (ref "X5") (pin "LEDY_K") (pinfunction "LEDY-_LEDY_K") (pintype "bidirectional"))
      (node (ref "X6") (pin "1") (pinfunction "SLEEVE_1") (pintype "bidirectional"))
      (node (ref "X7") (pin "GND1") (pinfunction "GND1_GND1") (pintype "bidirectional"))
      (node (ref "X7") (pin "GND2") (pinfunction "GND2_GND2") (pintype "bidirectional"))
      (node (ref "X7") (pin "GND3") (pinfunction "GND3_GND3") (pintype "bidirectional"))
      (node (ref "X7") (pin "GND4") (pinfunction "GND4_GND4") (pintype "bidirectional"))
      (node (ref "X7") (pin "SW_B") (pinfunction "SW_B_SW_B") (pintype "bidirectional"))
      (node (ref "X7") (pin "VSS") (pinfunction "GND_VSS") (pintype "bidirectional"))
      (node (ref "X8") (pin "N") (pinfunction "N_N") (pintype "bidirectional"))
      (node (ref "X9") (pin "18") (pinfunction "KL_18") (pintype "passive"))
      (node (ref "X9") (pin "20") (pinfunction "KL_20") (pintype "passive"))
      (node (ref "X9") (pin "9") (pinfunction "KL_9") (pintype "passive"))
    )
    (net (code "41") (name "I2S_BCK") (class "Default")
      (node (ref "IC4") (pin "13") (pinfunction "BCK_13") (pintype "input"))
      (node (ref "IC9") (pin "10") (pinfunction "PIN10_10") (pintype "bidirectional"))
    )
    (net (code "42") (name "I2S_DIN") (class "Default")
      (node (ref "IC4") (pin "14") (pinfunction "DIN_14") (pintype "input"))
      (node (ref "IC9") (pin "11") (pinfunction "PIN11_11") (pintype "bidirectional"))
    )
    (net (code "43") (name "I2S_LRCK") (class "Default")
      (node (ref "IC4") (pin "15") (pinfunction "LRCK_15") (pintype "input"))
      (node (ref "IC9") (pin "12") (pinfunction "PIN12_12") (pintype "bidirectional"))
    )
    (net (code "44") (name "ISP_MISO") (class "Default")
      (node (ref "IC12") (pin "16") (pinfunction "PB4(PCINT4/MISO)_16") (pintype "bidirectional"))
      (node (ref "X13") (pin "1") (pinfunction "1_1") (pintype "bidirectional"))
    )
    (net (code "45") (name "ISP_MOSI") (class "Default")
      (node (ref "IC12") (pin "15") (pinfunction "PB3(PCINT3/MOSI/OC2A)_15") (pintype "bidirectional"))
      (node (ref "X13") (pin "4") (pinfunction "4_4") (pintype "bidirectional"))
    )
    (net (code "46") (name "ISP_RES") (class "Default")
      (node (ref "IC12") (pin "29") (pinfunction "PC6(#RESET/PCINT14)_29") (pintype "bidirectional"))
      (node (ref "R49") (pin "1") (pinfunction "1_1") (pintype "passive"))
      (node (ref "X13") (pin "5") (pinfunction "5_5") (pintype "bidirectional"))
    )
    (net (code "47") (name "ISP_SCK") (class "Default")
      (node (ref "IC12") (pin "17") (pinfunction "PB5(SCK/PCINT5)_17") (pintype "bidirectional"))
      (node (ref "X13") (pin "3") (pinfunction "3_3") (pintype "bidirectional"))
    )
    (net (code "48") (name "JTAG_TCK") (class "Default")
      (node (ref "IC9") (pin "18") (pinfunction "PIN18_18") (pintype "bidirectional"))
      (node (ref "R38") (pin "1") (pinfunction "1_1") (pintype "passive"))
      (node (ref "X11") (pin "1") (pinfunction "KL_1") (pintype "passive"))
    )
    (net (code "49") (name "JTAG_TDI") (class "Default")
      (node (ref "IC9") (pin "19") (pinfunction "PIN19_19") (pintype "bidirectional"))
      (node (ref "R37") (pin "1") (pinfunction "1_1") (pintype "passive"))
      (node (ref "X11") (pin "9") (pinfunction "KL_9") (pintype "passive"))
    )
    (net (code "50") (name "JTAG_TDO") (class "Default")
      (node (ref "IC9") (pin "20") (pinfunction "PIN20_20") (pintype "bidirectional"))
      (node (ref "X11") (pin "3") (pinfunction "KL_3") (pintype "passive"))
    )
    (net (code "51") (name "JTAG_TMS") (class "Default")
      (node (ref "IC9") (pin "16") (pinfunction "PIN16_16") (pintype "bidirectional"))
      (node (ref "R36") (pin "1") (pinfunction "1_1") (pintype "passive"))
      (node (ref "X11") (pin "5") (pinfunction "KL_5") (pintype "passive"))
    )
    (net (code "52") (name "KB_CLK") (class "Default")
      (node (ref "IC9") (pin "124") (pinfunction "PIN124_124") (pintype "bidirectional"))
      (node (ref "R18") (pin "1") (pinfunction "1_1") (pintype "passive"))
    )
    (net (code "53") (name "KB_DAT") (class "Default")
      (node (ref "IC9") (pin "123") (pinfunction "PIN123_123") (pintype "bidirectional"))
      (node (ref "R16") (pin "1") (pinfunction "1_1") (pintype "passive"))
    )
    (net (code "54") (name "LEDG") (class "Default")
      (node (ref "IC3") (pin "27") (pinfunction "LEDA_27") (pintype "output"))
      (node (ref "R31") (pin "1") (pinfunction "1_1") (pintype "passive"))
    )
    (net (code "55") (name "LEDY") (class "Default")
      (node (ref "IC3") (pin "26") (pinfunction "LEDB_26") (pintype "output"))
      (node (ref "R30") (pin "1") (pinfunction "1_1") (pintype "passive"))
    )
    (net (code "56") (name "MS_CLK") (class "Default")
      (node (ref "IC9") (pin "121") (pinfunction "PIN121_121") (pintype "bidirectional"))
      (node (ref "R17") (pin "1") (pinfunction "1_1") (pintype "passive"))
    )
    (net (code "57") (name "MS_DAT") (class "Default")
      (node (ref "IC9") (pin "122") (pinfunction "PIN122_122") (pintype "bidirectional"))
      (node (ref "R15") (pin "1") (pinfunction "1_1") (pintype "passive"))
    )
    (net (code "58") (name "NCONFIG") (class "Default")
      (node (ref "IC9") (pin "129") (pinfunction "PIN129_129") (pintype "bidirectional"))
      (node (ref "R41") (pin "1") (pinfunction "1_1") (pintype "passive"))
    )
    (net (code "59") (name "NSTATUS") (class "Default")
      (node (ref "IC9") (pin "136") (pinfunction "PIN136_136") (pintype "bidirectional"))
      (node (ref "R43") (pin "1") (pinfunction "1_1") (pintype "passive"))
    )
    (net (code "60") (name "Net-(C3-Pad1)") (class "Default")
      (node (ref "C3") (pin "1") (pinfunction "1_1") (pintype "passive"))
      (node (ref "R1") (pin "1") (pinfunction "1_1") (pintype "passive"))
      (node (ref "X1") (pin "2") (pinfunction "2_2") (pintype "input"))
    )
    (net (code "61") (name "Net-(C4-Pad1)") (class "Default")
      (node (ref "C4") (pin "1") (pinfunction "1_1") (pintype "passive"))
      (node (ref "R2") (pin "1") (pinfunction "1_1") (pintype "passive"))
      (node (ref "X1") (pin "3") (pinfunction "3_3") (pintype "input"))
    )
    (net (code "62") (name "Net-(C24-Pad1)") (class "Default")
      (node (ref "C24") (pin "1") (pinfunction "1_1") (pintype "passive"))
      (node (ref "R24") (pin "1") (pinfunction "1_1") (pintype "passive"))
      (node (ref "R25") (pin "1") (pinfunction "1_1") (pintype "passive"))
    )
    (net (code "63") (name "Net-(FB2-P$2)") (class "Default")
      (node (ref "C44") (pin "1") (pinfunction "1_1") (pintype "passive"))
      (node (ref "C45") (pin "1") (pinfunction "1_1") (pintype "passive"))
      (node (ref "C46") (pin "1") (pinfunction "1_1") (pintype "passive"))
      (node (ref "C47") (pin "1") (pinfunction "1_1") (pintype "passive"))
      (node (ref "C48") (pin "1") (pinfunction "1_1") (pintype "passive"))
      (node (ref "FB2") (pin "2") (pinfunction "P$2_2") (pintype "passive"))
      (node (ref "IC9") (pin "107") (pinfunction "VCCA3_107") (pintype "bidirectional"))
      (node (ref "IC9") (pin "143") (pinfunction "VCCA4_143") (pintype "bidirectional"))
      (node (ref "IC9") (pin "2") (pinfunction "VCCA6_2") (pintype "bidirectional"))
      (node (ref "IC9") (pin "34") (pinfunction "VCCA2_34") (pintype "bidirectional"))
      (node (ref "IC9") (pin "35") (pinfunction "VCCA1_35") (pintype "bidirectional"))
      (node (ref "IC9") (pin "71") (pinfunction "VCCA5_71") (pintype "bidirectional"))
    )
    (net (code "64") (name "Net-(IC1A-C1+)") (class "Default")
      (node (ref "C1") (pin "2") (pinfunction "2_2") (pintype "passive"))
      (node (ref "IC1") (pin "28") (pinfunction "C1+_28") (pintype "passive"))
    )
    (net (code "65") (name "Net-(IC1A-C1-)") (class "Default")
      (node (ref "C1") (pin "1") (pinfunction "1_1") (pintype "passive"))
      (node (ref "IC1") (pin "24") (pinfunction "C1-_24") (pintype "passive"))
    )
    (net (code "66") (name "Net-(IC1A-C2+)") (class "Default")
      (node (ref "C2") (pin "2") (pinfunction "2_2") (pintype "passive"))
      (node (ref "IC1") (pin "1") (pinfunction "C2+_1") (pintype "passive"))
    )
    (net (code "67") (name "Net-(IC1A-C2-)") (class "Default")
      (node (ref "C2") (pin "1") (pinfunction "1_1") (pintype "passive"))
      (node (ref "IC1") (pin "2") (pinfunction "C2-_2") (pintype "passive"))
    )
    (net (code "68") (name "Net-(IC1A-V+)") (class "Default")
      (node (ref "C5") (pin "1") (pinfunction "1_1") (pintype "passive"))
      (node (ref "IC1") (pin "27") (pinfunction "V+_27") (pintype "passive"))
    )
    (net (code "69") (name "Net-(IC1A-V-)") (class "Default")
      (node (ref "C6") (pin "1") (pinfunction "1_1") (pintype "passive"))
      (node (ref "IC1") (pin "3") (pinfunction "V-_3") (pintype "passive"))
    )
    (net (code "70") (name "Net-(IC3-OSC1)") (class "Default")
      (node (ref "C22") (pin "1") (pinfunction "1_1") (pintype "passive"))
      (node (ref "IC3") (pin "23") (pinfunction "OSC1_23") (pintype "input"))
      (node (ref "Q1") (pin "3") (pinfunction "3_3") (pintype "passive"))
    )
    (net (code "71") (name "Net-(IC3-OSC2)") (class "Default")
      (node (ref "C21") (pin "1") (pinfunction "1_1") (pintype "passive"))
      (node (ref "IC3") (pin "24") (pinfunction "OSC2_24") (pintype "output"))
      (node (ref "Q1") (pin "1") (pinfunction "1_1") (pintype "passive"))
    )
    (net (code "72") (name "Net-(IC3-RBIAS)") (class "Default")
      (node (ref "IC3") (pin "14") (pinfunction "RBIAS_14") (pintype "input"))
      (node (ref "R23") (pin "1") (pinfunction "1_1") (pintype "passive"))
    )
    (net (code "73") (name "Net-(IC3-VCAP)") (class "Default")
      (node (ref "C17") (pin "1") (pinfunction "1_1") (pintype "passive"))
      (node (ref "IC3") (pin "1") (pinfunction "VCAP_1") (pintype "input"))
    )
    (net (code "74") (name "Net-(IC4A-OUTL)") (class "Default")
      (node (ref "IC4") (pin "6") (pinfunction "OUTL_6") (pintype "bidirectional"))
      (node (ref "R28") (pin "1") (pinfunction "1_1") (pintype "passive"))
    )
    (net (code "75") (name "Net-(IC4A-OUTR)") (class "Default")
      (node (ref "IC4") (pin "7") (pinfunction "OUTR_7") (pintype "bidirectional"))
      (node (ref "R29") (pin "1") (pinfunction "1_1") (pintype "passive"))
    )
    (net (code "76") (name "Net-(IC4B-CAPM)") (class "Default")
      (node (ref "C20") (pin "2") (pinfunction "2_2") (pintype "passive"))
      (node (ref "IC4") (pin "4") (pinfunction "CAPM_4") (pintype "bidirectional"))
    )
    (net (code "77") (name "Net-(IC4B-CAPP)") (class "Default")
      (node (ref "C20") (pin "1") (pinfunction "1_1") (pintype "passive"))
      (node (ref "IC4") (pin "2") (pinfunction "CAPP_2") (pintype "bidirectional"))
    )
    (net (code "78") (name "Net-(IC4B-LDOO)") (class "Default")
      (node (ref "C13") (pin "2") (pinfunction "2_2") (pintype "passive"))
      (node (ref "IC4") (pin "18") (pinfunction "LDOO_18") (pintype "bidirectional"))
    )
    (net (code "79") (name "Net-(IC4B-VNEG)") (class "Default")
      (node (ref "C19") (pin "2") (pinfunction "2_2") (pintype "passive"))
      (node (ref "IC4") (pin "5") (pinfunction "VNEG_5") (pintype "bidirectional"))
    )
    (net (code "80") (name "Net-(IC6-X1)") (class "Default")
      (node (ref "C35") (pin "1") (pinfunction "1_1") (pintype "passive"))
      (node (ref "IC6") (pin "1") (pinfunction "X1_1") (pintype "bidirectional"))
      (node (ref "Q2") (pin "4") (pinfunction "2_4") (pintype "passive"))
    )
    (net (code "81") (name "Net-(IC6-X2)") (class "Default")
      (node (ref "C36") (pin "1") (pinfunction "1_1") (pintype "passive"))
      (node (ref "IC6") (pin "2") (pinfunction "X2_2") (pintype "bidirectional"))
      (node (ref "Q2") (pin "1") (pinfunction "1_1") (pintype "passive"))
    )
    (net (code "82") (name "Net-(IC7-WP)") (class "Default")
      (node (ref "IC7") (pin "7") (pinfunction "WP_7") (pintype "bidirectional"))
      (node (ref "SJ4") (pin "2") (pinfunction "2_2") (pintype "passive"))
    )
    (net (code "83") (name "Net-(IC8-#WP)") (class "Default")
      (node (ref "IC8") (pin "3") (pinfunction "#WP_3") (pintype "bidirectional"))
      (node (ref "SJ5") (pin "2") (pinfunction "2_2") (pintype "passive"))
    )
    (net (code "84") (name "Net-(IC10-ADJ)") (class "Default")
      (node (ref "IC10") (pin "5") (pinfunction "ADJ_5") (pintype "bidirectional"))
      (node (ref "R45") (pin "2") (pinfunction "2_2") (pintype "passive"))
      (node (ref "R47") (pin "1") (pinfunction "1_1") (pintype "passive"))
    )
    (net (code "85") (name "Net-(IC11-ADJ)") (class "Default")
      (node (ref "IC11") (pin "5") (pinfunction "ADJ_5") (pintype "bidirectional"))
      (node (ref "R46") (pin "2") (pinfunction "2_2") (pintype "passive"))
      (node (ref "R48") (pin "1") (pinfunction "1_1") (pintype "passive"))
    )
    (net (code "86") (name "Net-(IC12-PC4(ADC4{slash}SDA{slash}PCINT12))") (class "Default")
      (node (ref "IC12") (pin "27") (pinfunction "PC4(ADC4/SDA/PCINT12)_27") (pintype "bidirectional"))
      (node (ref "R50") (pin "1") (pinfunction "1_1") (pintype "passive"))
      (node (ref "R51") (pin "2") (pinfunction "2_2") (pintype "passive"))
    )
    (net (code "87") (name "Net-(LED1-PadA)") (class "Default")
      (node (ref "LED1") (pin "A") (pinfunction "A_A") (pintype "passive"))
      (node (ref "R5") (pin "2") (pinfunction "2_2") (pintype "passive"))
    )
    (net (code "88") (name "Net-(LED2-PadC)") (class "Default")
      (node (ref "LED2") (pin "C") (pinfunction "C_C") (pintype "passive"))
      (node (ref "R39") (pin "1") (pinfunction "1_1") (pintype "passive"))
    )
    (net (code "89") (name "Net-(LED3-PadC)") (class "Default")
      (node (ref "LED3") (pin "C") (pinfunction "C_C") (pintype "passive"))
      (node (ref "R40") (pin "1") (pinfunction "1_1") (pintype "passive"))
    )
    (net (code "90") (name "Net-(R3-Pad2)") (class "Default")
      (node (ref "R3") (pin "2") (pinfunction "2_2") (pintype "passive"))
      (node (ref "X1") (pin "1") (pinfunction "1_1") (pintype "input"))
    )
    (net (code "91") (name "Net-(R6-Pad2)") (class "Default")
      (node (ref "R6") (pin "2") (pinfunction "2_2") (pintype "passive"))
      (node (ref "R7") (pin "2") (pinfunction "2_2") (pintype "passive"))
      (node (ref "R8") (pin "2") (pinfunction "2_2") (pintype "passive"))
      (node (ref "X3") (pin "1") (pinfunction "1_1") (pintype "passive"))
    )
    (net (code "92") (name "Net-(R10-Pad2)") (class "Default")
      (node (ref "R10") (pin "2") (pinfunction "2_2") (pintype "passive"))
      (node (ref "R11") (pin "2") (pinfunction "2_2") (pintype "passive"))
      (node (ref "R9") (pin "2") (pinfunction "2_2") (pintype "passive"))
      (node (ref "X3") (pin "2") (pinfunction "2_2") (pintype "passive"))
    )
    (net (code "93") (name "Net-(R12-Pad2)") (class "Default")
      (node (ref "R12") (pin "2") (pinfunction "2_2") (pintype "passive"))
      (node (ref "R13") (pin "2") (pinfunction "2_2") (pintype "passive"))
      (node (ref "R14") (pin "2") (pinfunction "2_2") (pintype "passive"))
      (node (ref "X3") (pin "3") (pinfunction "3_3") (pintype "passive"))
    )
    (net (code "94") (name "Net-(R44-Pad2)") (class "Default")
      (node (ref "R44") (pin "2") (pinfunction "2_2") (pintype "passive"))
      (node (ref "SJ6") (pin "2") (pinfunction "2_2") (pintype "passive"))
    )
    (net (code "95") (name "Net-(T1-B)") (class "Default")
      (node (ref "R35") (pin "2") (pinfunction "2_2") (pintype "passive"))
      (node (ref "T1") (pin "2") (pinfunction "B_2") (pintype "passive"))
    )
    (net (code "96") (name "Net-(T1-C)") (class "Default")
      (node (ref "Q3") (pin "N") (pinfunction "N_N") (pintype "bidirectional"))
      (node (ref "T1") (pin "3") (pinfunction "C_3") (pintype "passive"))
    )
    (net (code "97") (name "Net-(X4-1)") (class "Default")
      (node (ref "R15") (pin "2") (pinfunction "2_2") (pintype "passive"))
      (node (ref "R19") (pin "1") (pinfunction "1_1") (pintype "passive"))
      (node (ref "X4") (pin "2") (pinfunction "1_2") (pintype "bidirectional"))
    )
    (net (code "98") (name "Net-(X4-2)") (class "Default")
      (node (ref "R16") (pin "2") (pinfunction "2_2") (pintype "passive"))
      (node (ref "R20") (pin "1") (pinfunction "1_1") (pintype "passive"))
      (node (ref "X4") (pin "1") (pinfunction "2_1") (pintype "bidirectional"))
    )
    (net (code "99") (name "Net-(X4-3)") (class "Default")
      (node (ref "R17") (pin "2") (pinfunction "2_2") (pintype "passive"))
      (node (ref "R21") (pin "1") (pinfunction "1_1") (pintype "passive"))
      (node (ref "X4") (pin "6") (pinfunction "3_6") (pintype "bidirectional"))
    )
    (net (code "100") (name "Net-(X4-4)") (class "Default")
      (node (ref "R18") (pin "2") (pinfunction "2_2") (pintype "passive"))
      (node (ref "R22") (pin "1") (pinfunction "1_1") (pintype "passive"))
      (node (ref "X4") (pin "5") (pinfunction "4_5") (pintype "bidirectional"))
    )
    (net (code "101") (name "Net-(X5-LEDG+)") (class "Default")
      (node (ref "R31") (pin "2") (pinfunction "2_2") (pintype "passive"))
      (node (ref "X5") (pin "LEDG_A") (pinfunction "LEDG+_LEDG_A") (pintype "bidirectional"))
    )
    (net (code "102") (name "Net-(X5-LEDY+)") (class "Default")
      (node (ref "R30") (pin "2") (pinfunction "2_2") (pintype "passive"))
      (node (ref "X5") (pin "LEDY_A") (pinfunction "LEDY+_LEDY_A") (pintype "bidirectional"))
    )
    (net (code "103") (name "Net-(X5-RX_TX_0)") (class "Default")
      (node (ref "C25") (pin "1") (pinfunction "1_1") (pintype "passive"))
      (node (ref "R26") (pin "1") (pinfunction "1_1") (pintype "passive"))
      (node (ref "R27") (pin "1") (pinfunction "1_1") (pintype "passive"))
      (node (ref "X5") (pin "3") (pinfunction "RX_TX_0_3") (pintype "bidirectional"))
    )
    (net (code "104") (name "Net-(X6-RING)") (class "Default")
      (node (ref "C26") (pin "1") (pinfunction "1_1") (pintype "passive"))
      (node (ref "R29") (pin "2") (pinfunction "2_2") (pintype "passive"))
      (node (ref "X6") (pin "3") (pinfunction "RING_3") (pintype "bidirectional"))
    )
    (net (code "105") (name "Net-(X6-TIP)") (class "Default")
      (node (ref "C27") (pin "1") (pinfunction "1_1") (pintype "passive"))
      (node (ref "R28") (pin "2") (pinfunction "2_2") (pintype "passive"))
      (node (ref "X6") (pin "2") (pinfunction "TIP_2") (pintype "bidirectional"))
    )
    (net (code "106") (name "POWER_BTN") (class "Default")
      (node (ref "IC12") (pin "10") (pinfunction "PD6(PCINT22/OC0A/AIN0)_10") (pintype "bidirectional"))
      (node (ref "S2") (pin "1") (pinfunction "1_1") (pintype "passive"))
      (node (ref "X10") (pin "4") (pinfunction "4_4") (pintype "bidirectional"))
    )
    (net (code "107") (name "POWER_ON") (class "Default")
      (node (ref "IC10") (pin "1") (pinfunction "EN_1") (pintype "bidirectional"))
      (node (ref "IC12") (pin "8") (pinfunction "PB7(PCINT7/XTAL2/TOSC2)_8") (pintype "bidirectional"))
      (node (ref "X9") (pin "13") (pinfunction "KL_13") (pintype "passive"))
    )
    (net (code "108") (name "PWRMNG_RES") (class "Default")
      (node (ref "IC12") (pin "32") (pinfunction "PD2(INT0/PCINT18)_32") (pintype "bidirectional"))
      (node (ref "IC9") (pin "100") (pinfunction "PIN100_100") (pintype "bidirectional"))
    )
    (net (code "109") (name "PWRMNG_RX") (class "Default")
      (node (ref "IC12") (pin "31") (pinfunction "PD1(TXD/PCINT17)_31") (pintype "bidirectional"))
      (node (ref "IC9") (pin "101") (pinfunction "PIN101_101") (pintype "bidirectional"))
    )
    (net (code "110") (name "PWRMNG_TX") (class "Default")
      (node (ref "IC12") (pin "30") (pinfunction "PD0(RXD/PCINT16)_30") (pintype "bidirectional"))
      (node (ref "IC9") (pin "102") (pinfunction "PIN102_102") (pintype "bidirectional"))
    )
    (net (code "111") (name "RES") (class "Default")
      (node (ref "IC3") (pin "10") (pinfunction "~{RESET}_10") (pintype "input"))
      (node (ref "IC9") (pin "77") (pinfunction "PIN77_77") (pintype "bidirectional"))
      (node (ref "X9") (pin "7") (pinfunction "KL_7") (pintype "passive"))
    )
    (net (code "112") (name "RESET_BTN") (class "Default")
      (node (ref "IC12") (pin "11") (pinfunction "PD7(PCINT23/AIN1)_11") (pintype "bidirectional"))
      (node (ref "S1") (pin "1") (pinfunction "1_1") (pintype "passive"))
      (node (ref "X10") (pin "2") (pinfunction "2_2") (pintype "bidirectional"))
    )
    (net (code "113") (name "RI1") (class "Default")
      (node (ref "IC1") (pin "8") (pinfunction "R5IN_8") (pintype "input"))
      (node (ref "X2") (pin "9") (pinfunction "9_9") (pintype "passive"))
    )
    (net (code "114") (name "RTC_MFP") (class "Default")
      (node (ref "IC6") (pin "7") (pinfunction "MFP_7") (pintype "bidirectional"))
      (node (ref "IC9") (pin "8") (pinfunction "PIN8_8") (pintype "bidirectional"))
    )
    (net (code "115") (name "RTS1") (class "Default")
      (node (ref "IC1") (pin "9") (pinfunction "T1OUT_9") (pintype "output"))
      (node (ref "X2") (pin "7") (pinfunction "7_7") (pintype "passive"))
    )
    (net (code "116") (name "RXD1") (class "Default")
      (node (ref "IC1") (pin "6") (pinfunction "R3IN_6") (pintype "input"))
      (node (ref "X2") (pin "2") (pinfunction "2_2") (pintype "passive"))
    )
    (net (code "117") (name "SCL") (class "Default")
      (node (ref "IC6") (pin "6") (pinfunction "SCL_6") (pintype "bidirectional"))
      (node (ref "IC7") (pin "6") (pinfunction "SCL_6") (pintype "bidirectional"))
      (node (ref "IC9") (pin "7") (pinfunction "PIN7_7") (pintype "bidirectional"))
      (node (ref "R33") (pin "2") (pinfunction "2_2") (pintype "passive"))
    )
    (net (code "118") (name "SDA") (class "Default")
      (node (ref "IC6") (pin "5") (pinfunction "SDA_5") (pintype "bidirectional"))
      (node (ref "IC7") (pin "5") (pinfunction "SDA_5") (pintype "bidirectional"))
      (node (ref "IC9") (pin "6") (pinfunction "PIN6_6") (pintype "bidirectional"))
      (node (ref "R34") (pin "2") (pinfunction "2_2") (pintype "passive"))
    )
    (net (code "119") (name "SDRAM_A0") (class "Default")
      (node (ref "IC5") (pin "23") (pinfunction "A0_23") (pintype "input"))
      (node (ref "IC9") (pin "61") (pinfunction "PIN61_61") (pintype "bidirectional"))
    )
    (net (code "120") (name "SDRAM_A1") (class "Default")
      (node (ref "IC5") (pin "24") (pinfunction "A1_24") (pintype "input"))
      (node (ref "IC9") (pin "62") (pinfunction "PIN62_62") (pintype "bidirectional"))
    )
    (net (code "121") (name "SDRAM_A2") (class "Default")
      (node (ref "IC5") (pin "25") (pinfunction "A2_25") (pintype "input"))
      (node (ref "IC9") (pin "64") (pinfunction "PIN64_64") (pintype "bidirectional"))
    )
    (net (code "122") (name "SDRAM_A3") (class "Default")
      (node (ref "IC5") (pin "26") (pinfunction "A3_26") (pintype "input"))
      (node (ref "IC9") (pin "65") (pinfunction "PIN65_65") (pintype "bidirectional"))
    )
    (net (code "123") (name "SDRAM_A4") (class "Default")
      (node (ref "IC5") (pin "29") (pinfunction "A4_29") (pintype "input"))
      (node (ref "IC9") (pin "47") (pinfunction "PIN47_47") (pintype "bidirectional"))
    )
    (net (code "124") (name "SDRAM_A5") (class "Default")
      (node (ref "IC5") (pin "30") (pinfunction "A5_30") (pintype "input"))
      (node (ref "IC9") (pin "46") (pinfunction "PIN46_46") (pintype "bidirectional"))
    )
    (net (code "125") (name "SDRAM_A6") (class "Default")
      (node (ref "IC5") (pin "31") (pinfunction "A6_31") (pintype "input"))
      (node (ref "IC9") (pin "45") (pinfunction "PIN45_45") (pintype "bidirectional"))
    )
    (net (code "126") (name "SDRAM_A7") (class "Default")
      (node (ref "IC5") (pin "32") (pinfunction "A7_32") (pintype "input"))
      (node (ref "IC9") (pin "44") (pinfunction "PIN44_44") (pintype "bidirectional"))
    )
    (net (code "127") (name "SDRAM_A8") (class "Default")
      (node (ref "IC5") (pin "33") (pinfunction "A8_33") (pintype "input"))
      (node (ref "IC9") (pin "43") (pinfunction "PIN43_43") (pintype "bidirectional"))
    )
    (net (code "128") (name "SDRAM_A9") (class "Default")
      (node (ref "IC5") (pin "34") (pinfunction "A9_34") (pintype "input"))
      (node (ref "IC9") (pin "41") (pinfunction "PIN41_41") (pintype "bidirectional"))
    )
    (net (code "129") (name "SDRAM_A10") (class "Default")
      (node (ref "IC5") (pin "22") (pinfunction "A10_22") (pintype "input"))
      (node (ref "IC9") (pin "60") (pinfunction "PIN60_60") (pintype "bidirectional"))
    )
    (net (code "130") (name "SDRAM_A11") (class "Default")
      (node (ref "IC5") (pin "35") (pinfunction "A11_35") (pintype "input"))
      (node (ref "IC9") (pin "39") (pinfunction "PIN39_39") (pintype "bidirectional"))
    )
    (net (code "131") (name "SDRAM_A12") (class "Default")
      (node (ref "IC5") (pin "36") (pinfunction "A12_36") (pintype "input"))
      (node (ref "IC9") (pin "38") (pinfunction "PIN38_38") (pintype "bidirectional"))
    )
    (net (code "132") (name "SDRAM_BA0") (class "Default")
      (node (ref "IC5") (pin "20") (pinfunction "BA0_20") (pintype "input"))
      (node (ref "IC9") (pin "58") (pinfunction "PIN58_58") (pintype "bidirectional"))
    )
    (net (code "133") (name "SDRAM_BA1") (class "Default")
      (node (ref "IC5") (pin "21") (pinfunction "BA1_21") (pintype "input"))
      (node (ref "IC9") (pin "59") (pinfunction "PIN59_59") (pintype "bidirectional"))
    )
    (net (code "134") (name "SDRAM_CAS") (class "Default")
      (node (ref "IC5") (pin "17") (pinfunction "CAS#_17") (pintype "input"))
      (node (ref "IC9") (pin "56") (pinfunction "PIN56_56") (pintype "bidirectional"))
    )
    (net (code "135") (name "SDRAM_CLK") (class "Default")
      (node (ref "IC5") (pin "38") (pinfunction "CLK_38") (pintype "input"))
      (node (ref "IC9") (pin "33") (pinfunction "PIN33_33") (pintype "bidirectional"))
    )
    (net (code "136") (name "SDRAM_DQ0") (class "Default")
      (node (ref "IC5") (pin "2") (pinfunction "DQ0_2") (pintype "bidirectional"))
      (node (ref "IC9") (pin "48") (pinfunction "PIN48_48") (pintype "bidirectional"))
    )
    (net (code "137") (name "SDRAM_DQ1") (class "Default")
      (node (ref "IC5") (pin "5") (pinfunction "DQ1_5") (pintype "bidirectional"))
      (node (ref "IC9") (pin "50") (pinfunction "PIN50_50") (pintype "bidirectional"))
    )
    (net (code "138") (name "SDRAM_DQ2") (class "Default")
      (node (ref "IC5") (pin "8") (pinfunction "DQ2_8") (pintype "bidirectional"))
      (node (ref "IC9") (pin "52") (pinfunction "PIN52_52") (pintype "bidirectional"))
    )
    (net (code "139") (name "SDRAM_DQ3") (class "Default")
      (node (ref "IC5") (pin "11") (pinfunction "DQ3_11") (pintype "bidirectional"))
      (node (ref "IC9") (pin "54") (pinfunction "PIN54_54") (pintype "bidirectional"))
    )
    (net (code "140") (name "SDRAM_DQ4") (class "Default")
      (node (ref "IC5") (pin "44") (pinfunction "DQ4_44") (pintype "bidirectional"))
      (node (ref "IC9") (pin "32") (pinfunction "PIN31_32") (pintype "bidirectional"))
    )
    (net (code "141") (name "SDRAM_DQ5") (class "Default")
      (node (ref "IC5") (pin "47") (pinfunction "DQ5_47") (pintype "bidirectional"))
      (node (ref "IC9") (pin "30") (pinfunction "PIN30_30") (pintype "bidirectional"))
    )
    (net (code "142") (name "SDRAM_DQ6") (class "Default")
      (node (ref "IC5") (pin "50") (pinfunction "DQ6_50") (pintype "bidirectional"))
      (node (ref "IC9") (pin "29") (pinfunction "PIN29_29") (pintype "bidirectional"))
    )
    (net (code "143") (name "SDRAM_DQ7") (class "Default")
      (node (ref "IC5") (pin "53") (pinfunction "DQ7_53") (pintype "bidirectional"))
      (node (ref "IC9") (pin "28") (pinfunction "PIN28_28") (pintype "bidirectional"))
    )
    (net (code "144") (name "SDRAM_RAS") (class "Default")
      (node (ref "IC5") (pin "18") (pinfunction "RAS#_18") (pintype "input"))
      (node (ref "IC9") (pin "57") (pinfunction "PIN57_57") (pintype "bidirectional"))
    )
    (net (code "145") (name "SDRAM_WE") (class "Default")
      (node (ref "IC5") (pin "16") (pinfunction "WE#_16") (pintype "input"))
      (node (ref "IC9") (pin "55") (pinfunction "PIN55_55") (pintype "bidirectional"))
    )
    (net (code "146") (name "SD_CLK") (class "Default")
      (node (ref "IC9") (pin "74") (pinfunction "PIN74_74") (pintype "bidirectional"))
      (node (ref "X7") (pin "CLK") (pinfunction "CLK_CLK") (pintype "bidirectional"))
    )
    (net (code "147") (name "SD_CMD") (class "Default")
      (node (ref "IC9") (pin "70") (pinfunction "PIN70_70") (pintype "bidirectional"))
      (node (ref "X7") (pin "CMD") (pinfunction "CMD_CMD") (pintype "bidirectional"))
    )
    (net (code "148") (name "SD_DAT0") (class "Default")
      (node (ref "IC9") (pin "75") (pinfunction "PIN75_75") (pintype "bidirectional"))
      (node (ref "X7") (pin "DAT0") (pinfunction "DAT0_DAT0") (pintype "bidirectional"))
    )
    (net (code "149") (name "SD_DAT1") (class "Default")
      (node (ref "IC9") (pin "76") (pinfunction "PIN76_76") (pintype "bidirectional"))
      (node (ref "X7") (pin "DAT1") (pinfunction "DAT1_DAT1") (pintype "bidirectional"))
    )
    (net (code "150") (name "SD_DAT2") (class "Default")
      (node (ref "IC9") (pin "66") (pinfunction "PIN66_66") (pintype "bidirectional"))
      (node (ref "X7") (pin "DAT2") (pinfunction "DAT2_DAT2") (pintype "bidirectional"))
    )
    (net (code "151") (name "SD_DAT3") (class "Default")
      (node (ref "IC9") (pin "69") (pinfunction "PIN69_69") (pintype "bidirectional"))
      (node (ref "X7") (pin "CD/DAT3") (pinfunction "CD/DAT3_CD/DAT3") (pintype "bidirectional"))
    )
    (net (code "152") (name "SD_SW") (class "Default")
      (node (ref "IC12") (pin "7") (pinfunction "PB6(PCINT6/XTAL1/TOSC1)_7") (pintype "bidirectional"))
      (node (ref "R32") (pin "1") (pinfunction "1_1") (pintype "passive"))
      (node (ref "X7") (pin "SW_A") (pinfunction "SW_A_SW_A") (pintype "bidirectional"))
    )
    (net (code "153") (name "SPEAKER") (class "Default")
      (node (ref "IC12") (pin "14") (pinfunction "PB2(PCINT2/#SS/OC1B)_14") (pintype "bidirectional"))
      (node (ref "R35") (pin "1") (pinfunction "1_1") (pintype "passive"))
    )
    (net (code "154") (name "TPIN_N") (class "Default")
      (node (ref "IC3") (pin "12") (pinfunction "TPIN-_12") (pintype "input"))
      (node (ref "R25") (pin "2") (pinfunction "2_2") (pintype "passive"))
      (node (ref "X5") (pin "8") (pinfunction "RX-_8") (pintype "bidirectional"))
    )
    (net (code "155") (name "TPIN_P") (class "Default")
      (node (ref "IC3") (pin "13") (pinfunction "TPIN+_13") (pintype "input"))
      (node (ref "R24") (pin "2") (pinfunction "2_2") (pintype "passive"))
      (node (ref "X5") (pin "7") (pinfunction "RX+_7") (pintype "bidirectional"))
    )
    (net (code "156") (name "TPOUT_N") (class "Default")
      (node (ref "IC3") (pin "16") (pinfunction "TPOUT-_16") (pintype "output"))
      (node (ref "R27") (pin "2") (pinfunction "2_2") (pintype "passive"))
      (node (ref "X5") (pin "2") (pinfunction "TX-_2") (pintype "bidirectional"))
    )
    (net (code "157") (name "TPOUT_P") (class "Default")
      (node (ref "IC3") (pin "17") (pinfunction "TPOUT+_17") (pintype "output"))
      (node (ref "R26") (pin "2") (pinfunction "2_2") (pintype "passive"))
      (node (ref "X5") (pin "1") (pinfunction "TX+_1") (pintype "bidirectional"))
    )
    (net (code "158") (name "TXD1") (class "Default")
      (node (ref "IC1") (pin "10") (pinfunction "T2OUT_10") (pintype "output"))
      (node (ref "X2") (pin "3") (pinfunction "3_3") (pintype "passive"))
    )
    (net (code "159") (name "UART0_CBUS0") (class "Default")
      (node (ref "IC2") (pin "15") (pinfunction "CBUS0_15") (pintype "bidirectional"))
      (node (ref "IC9") (pin "78") (pinfunction "PIN78_78") (pintype "bidirectional"))
    )
    (net (code "160") (name "UART0_CBUS1") (class "Default")
      (node (ref "IC2") (pin "14") (pinfunction "CBUS1_14") (pintype "bidirectional"))
      (node (ref "IC9") (pin "79") (pinfunction "PIN79_79") (pintype "bidirectional"))
    )
    (net (code "161") (name "UART0_LED") (class "Default")
      (node (ref "IC2") (pin "16") (pinfunction "CBUS3_16") (pintype "bidirectional"))
      (node (ref "LED1") (pin "C") (pinfunction "C_C") (pintype "passive"))
      (node (ref "X10") (pin "5") (pinfunction "5_5") (pintype "bidirectional"))
    )
    (net (code "162") (name "UART0_RXD") (class "Default")
      (node (ref "IC2") (pin "1") (pinfunction "TXD_1") (pintype "bidirectional"))
      (node (ref "IC9") (pin "81") (pinfunction "PIN81_81") (pintype "bidirectional"))
    )
    (net (code "163") (name "UART0_TXD") (class "Default")
      (node (ref "IC2") (pin "4") (pinfunction "RXD_4") (pintype "bidirectional"))
      (node (ref "IC9") (pin "80") (pinfunction "PIN80_80") (pintype "bidirectional"))
    )
    (net (code "164") (name "UART1_CTS") (class "Default")
      (node (ref "IC1") (pin "16") (pinfunction "R4OUT_16") (pintype "output"))
      (node (ref "IC9") (pin "132") (pinfunction "PIN132_132") (pintype "bidirectional"))
    )
    (net (code "165") (name "UART1_DCD") (class "Default")
      (node (ref "IC1") (pin "19") (pinfunction "R1OUT_19") (pintype "output"))
      (node (ref "IC9") (pin "127") (pinfunction "PIN127_127") (pintype "bidirectional"))
    )
    (net (code "166") (name "UART1_DSR") (class "Default")
      (node (ref "IC1") (pin "18") (pinfunction "R2OUT_18") (pintype "output"))
      (node (ref "IC9") (pin "130") (pinfunction "PIN130_130") (pintype "bidirectional"))
    )
    (net (code "167") (name "UART1_DTR") (class "Default")
      (node (ref "IC1") (pin "12") (pinfunction "T3IN_12") (pintype "input"))
      (node (ref "IC9") (pin "135") (pinfunction "PIN135_135") (pintype "bidirectional"))
    )
    (net (code "168") (name "UART1_RI") (class "Default")
      (node (ref "IC1") (pin "15") (pinfunction "R5OUT_15") (pintype "output"))
      (node (ref "IC9") (pin "134") (pinfunction "PIN134_134") (pintype "bidirectional"))
    )
    (net (code "169") (name "UART1_RTS") (class "Default")
      (node (ref "IC1") (pin "14") (pinfunction "T1IN_14") (pintype "input"))
      (node (ref "IC9") (pin "141") (pinfunction "PIN141_141") (pintype "bidirectional"))
    )
    (net (code "170") (name "UART1_RXD") (class "Default")
      (node (ref "IC1") (pin "17") (pinfunction "R3OUT_17") (pintype "output"))
      (node (ref "IC9") (pin "131") (pinfunction "PIN131_131") (pintype "bidirectional"))
    )
    (net (code "171") (name "UART1_TXD") (class "Default")
      (node (ref "IC1") (pin "13") (pinfunction "T2IN_13") (pintype "input"))
      (node (ref "IC9") (pin "140") (pinfunction "PIN140_140") (pintype "bidirectional"))
    )
    (net (code "172") (name "USBDM") (class "Default")
      (node (ref "IC2") (pin "9") (pinfunction "USBDM_9") (pintype "bidirectional"))
      (node (ref "R1") (pin "2") (pinfunction "2_2") (pintype "passive"))
    )
    (net (code "173") (name "USBDP") (class "Default")
      (node (ref "IC2") (pin "8") (pinfunction "USBDP_8") (pintype "bidirectional"))
      (node (ref "R2") (pin "2") (pinfunction "2_2") (pintype "passive"))
    )
    (net (code "174") (name "VBAT") (class "Default")
      (node (ref "IC6") (pin "3") (pinfunction "VBAT_3") (pintype "bidirectional"))
      (node (ref "R50") (pin "2") (pinfunction "2_2") (pintype "passive"))
      (node (ref "X8") (pin "P1") (pinfunction "P_P1") (pintype "bidirectional"))
    )
    (net (code "175") (name "VBUS_SENSE") (class "Default")
      (node (ref "IC2") (pin "7") (pinfunction "CBUS2_7") (pintype "bidirectional"))
      (node (ref "R3") (pin "1") (pinfunction "1_1") (pintype "passive"))
      (node (ref "R4") (pin "2") (pinfunction "2_2") (pintype "passive"))
    )
    (net (code "176") (name "VCC") (class "Default")
      (node (ref "C64") (pin "+") (pinfunction "+_+") (pintype "passive"))
      (node (ref "IC10") (pin "2") (pinfunction "VIN_2") (pintype "bidirectional"))
      (node (ref "IC13") (pin "3") (pinfunction "VIN_3") (pintype "bidirectional"))
      (node (ref "X12") (pin "1") (pinfunction "3_1") (pintype "passive"))
      (node (ref "X9") (pin "4") (pinfunction "KL_4") (pintype "passive"))
    )
    (net (code "177") (name "VGA_B0") (class "Default")
      (node (ref "IC9") (pin "106") (pinfunction "PIN106_106") (pintype "bidirectional"))
      (node (ref "R12") (pin "1") (pinfunction "1_1") (pintype "passive"))
      (node (ref "R13") (pin "1") (pinfunction "1_1") (pintype "passive"))
    )
    (net (code "178") (name "VGA_B1") (class "Default")
      (node (ref "IC9") (pin "105") (pinfunction "PIN105_105") (pintype "bidirectional"))
      (node (ref "R14") (pin "1") (pinfunction "1_1") (pintype "passive"))
    )
    (net (code "179") (name "VGA_G0") (class "Default")
      (node (ref "IC9") (pin "112") (pinfunction "PIN112_112") (pintype "bidirectional"))
      (node (ref "R9") (pin "1") (pinfunction "1_1") (pintype "passive"))
    )
    (net (code "180") (name "VGA_G1") (class "Default")
      (node (ref "IC9") (pin "111") (pinfunction "PIN111_111") (pintype "bidirectional"))
      (node (ref "R10") (pin "1") (pinfunction "1_1") (pintype "passive"))
    )
    (net (code "181") (name "VGA_G2") (class "Default")
      (node (ref "IC9") (pin "110") (pinfunction "PIN110_110") (pintype "bidirectional"))
      (node (ref "R11") (pin "1") (pinfunction "1_1") (pintype "passive"))
    )
    (net (code "182") (name "VGA_HS") (class "Default")
      (node (ref "IC9") (pin "120") (pinfunction "PIN120_120") (pintype "bidirectional"))
      (node (ref "X3") (pin "13") (pinfunction "13_13") (pintype "passive"))
    )
    (net (code "183") (name "VGA_R0") (class "Default")
      (node (ref "IC9") (pin "118") (pinfunction "PIN118_118") (pintype "bidirectional"))
      (node (ref "R6") (pin "1") (pinfunction "1_1") (pintype "passive"))
    )
    (net (code "184") (name "VGA_R1") (class "Default")
      (node (ref "IC9") (pin "114") (pinfunction "PIN114_114") (pintype "bidirectional"))
      (node (ref "R7") (pin "1") (pinfunction "1_1") (pintype "passive"))
    )
    (net (code "185") (name "VGA_R2") (class "Default")
      (node (ref "IC9") (pin "113") (pinfunction "PIN113_113") (pintype "bidirectional"))
      (node (ref "R8") (pin "1") (pinfunction "1_1") (pintype "passive"))
    )
    (net (code "186") (name "VGA_VS") (class "Default")
      (node (ref "IC9") (pin "119") (pinfunction "PIN119_119") (pintype "bidirectional"))
      (node (ref "X3") (pin "14") (pinfunction "14_14") (pintype "passive"))
    )
    (net (code "187") (name "unconnected-(IC1A-R2OUTB-Pad20)") (class "Default")
      (node (ref "IC1") (pin "20") (pinfunction "R2OUTB_20") (pintype "output"))
    )
    (net (code "188") (name "unconnected-(IC1A-~{INVALID}-Pad21)") (class "Default")
      (node (ref "IC1") (pin "21") (pinfunction "~{INVALID}_21") (pintype "output"))
    )
    (net (code "189") (name "unconnected-(IC2-CTS#-Pad6)") (class "Default")
      (node (ref "IC2") (pin "6") (pinfunction "CTS#_6") (pintype "bidirectional"))
    )
    (net (code "190") (name "unconnected-(IC2-RTS#-Pad2)") (class "Default")
      (node (ref "IC2") (pin "2") (pinfunction "RTS#_2") (pintype "bidirectional"))
    )
    (net (code "191") (name "unconnected-(IC3-CLKOUT-Pad3)") (class "Default")
      (node (ref "IC3") (pin "3") (pinfunction "CLKOUT_3") (pintype "output"))
    )
    (net (code "192") (name "unconnected-(IC3-NC*-Pad5)") (class "Default")
      (node (ref "IC3") (pin "5") (pinfunction "NC*_5") (pintype "output"))
    )
    (net (code "193") (name "unconnected-(IC7-NC1-Pad1)") (class "Default")
      (node (ref "IC7") (pin "1") (pinfunction "NC1_1") (pintype "no_connect"))
    )
    (net (code "194") (name "unconnected-(IC7-NC2-Pad2)") (class "Default")
      (node (ref "IC7") (pin "2") (pinfunction "NC2_2") (pintype "no_connect"))
    )
    (net (code "195") (name "unconnected-(IC7-NC3-Pad3)") (class "Default")
      (node (ref "IC7") (pin "3") (pinfunction "NC3_3") (pintype "no_connect"))
    )
    (net (code "196") (name "unconnected-(IC9A-ADC_VREF-Pad5)") (class "Default")
      (node (ref "IC9") (pin "5") (pinfunction "ADC_VREF_5") (pintype "bidirectional"))
    )
    (net (code "197") (name "unconnected-(IC12-AREF-Pad20)") (class "Default")
      (node (ref "IC12") (pin "20") (pinfunction "AREF_20") (pintype "input"))
    )
    (net (code "198") (name "unconnected-(IC12-PB0(PCINT0{slash}CLKO{slash}ICP1)-Pad12)") (class "Default")
      (node (ref "IC12") (pin "12") (pinfunction "PB0(PCINT0/CLKO/ICP1)_12") (pintype "bidirectional"))
    )
    (net (code "199") (name "unconnected-(IC12-PB1(PCINT1{slash}OC1A)-Pad13)") (class "Default")
      (node (ref "IC12") (pin "13") (pinfunction "PB1(PCINT1/OC1A)_13") (pintype "bidirectional"))
    )
    (net (code "200") (name "unconnected-(IC12-PC0(ADC0{slash}PCINT8)-Pad23)") (class "Default")
      (node (ref "IC12") (pin "23") (pinfunction "PC0(ADC0/PCINT8)_23") (pintype "bidirectional"))
    )
    (net (code "201") (name "unconnected-(IC12-PC1(ADC1{slash}PCINT9)-Pad24)") (class "Default")
      (node (ref "IC12") (pin "24") (pinfunction "PC1(ADC1/PCINT9)_24") (pintype "bidirectional"))
    )
    (net (code "202") (name "unconnected-(IC12-PC2(ADC2{slash}PCINT10)-Pad25)") (class "Default")
      (node (ref "IC12") (pin "25") (pinfunction "PC2(ADC2/PCINT10)_25") (pintype "bidirectional"))
    )
    (net (code "203") (name "unconnected-(IC12-PC3(ADC3{slash}PCINT11)-Pad26)") (class "Default")
      (node (ref "IC12") (pin "26") (pinfunction "PC3(ADC3/PCINT11)_26") (pintype "bidirectional"))
    )
    (net (code "204") (name "unconnected-(IC12-PD3(PCINT19{slash}OC2B{slash}INT1)-Pad1)") (class "Default")
      (node (ref "IC12") (pin "1") (pinfunction "PD3(PCINT19/OC2B/INT1)_1") (pintype "bidirectional"))
    )
    (net (code "205") (name "unconnected-(IC12-PD4(PCINT20{slash}XCK{slash}T0)-Pad2)") (class "Default")
      (node (ref "IC12") (pin "2") (pinfunction "PD4(PCINT20/XCK/T0)_2") (pintype "bidirectional"))
    )
    (net (code "206") (name "unconnected-(IC12-PE0(ACO)-Pad3)") (class "Default")
      (node (ref "IC12") (pin "3") (pinfunction "PE0(ACO)_3") (pintype "bidirectional"))
    )
    (net (code "207") (name "unconnected-(IC12-PE1-Pad6)") (class "Default")
      (node (ref "IC12") (pin "6") (pinfunction "PE1_6") (pintype "bidirectional"))
    )
    (net (code "208") (name "unconnected-(IC12-PE2(ADC6)-Pad19)") (class "Default")
      (node (ref "IC12") (pin "19") (pinfunction "PE2(ADC6)_19") (pintype "bidirectional"))
    )
    (net (code "209") (name "unconnected-(IC12-PE3(ADC7)-Pad22)") (class "Default")
      (node (ref "IC12") (pin "22") (pinfunction "PE3(ADC7)_22") (pintype "bidirectional"))
    )
    (net (code "210") (name "unconnected-(S1-Pad2)") (class "Default")
      (node (ref "S1") (pin "2") (pinfunction "2_2") (pintype "passive"))
    )
    (net (code "211") (name "unconnected-(S2-Pad2)") (class "Default")
      (node (ref "S2") (pin "2") (pinfunction "2_2") (pintype "passive"))
    )
    (net (code "212") (name "unconnected-(X1-Pad4)") (class "Default")
      (node (ref "X1") (pin "4") (pinfunction "4_4") (pintype "input"))
    )
    (net (code "213") (name "unconnected-(X3-Pad4)") (class "Default")
      (node (ref "X3") (pin "4") (pinfunction "4_4") (pintype "passive"))
    )
    (net (code "214") (name "unconnected-(X3-Pad9)") (class "Default")
      (node (ref "X3") (pin "9") (pinfunction "9_9") (pintype "passive"))
    )
    (net (code "215") (name "unconnected-(X3-Pad11)") (class "Default")
      (node (ref "X3") (pin "11") (pinfunction "11_11") (pintype "passive"))
    )
    (net (code "216") (name "unconnected-(X3-Pad12)") (class "Default")
      (node (ref "X3") (pin "12") (pinfunction "12_12") (pintype "passive"))
    )
    (net (code "217") (name "unconnected-(X3-Pad15)") (class "Default")
      (node (ref "X3") (pin "15") (pinfunction "15_15") (pintype "passive"))
    )
    (net (code "218") (name "unconnected-(X5-NC1-Pad4)") (class "Default")
      (node (ref "X5") (pin "4") (pinfunction "NC1_4") (pintype "no_connect"))
    )
    (net (code "219") (name "unconnected-(X5-NC2-Pad5)") (class "Default")
      (node (ref "X5") (pin "5") (pinfunction "NC2_5") (pintype "no_connect"))
    )
    (net (code "220") (name "unconnected-(X5-NC3-Pad6)") (class "Default")
      (node (ref "X5") (pin "6") (pinfunction "NC3_6") (pintype "no_connect"))
    )
    (net (code "221") (name "unconnected-(X6-RING_SW-Pad5)") (class "Default")
      (node (ref "X6") (pin "5") (pinfunction "RING_SW_5") (pintype "bidirectional"))
    )
    (net (code "222") (name "unconnected-(X6-TIP_SW-Pad4)") (class "Default")
      (node (ref "X6") (pin "4") (pinfunction "TIP_SW_4") (pintype "bidirectional"))
    )
    (net (code "223") (name "unconnected-(X11G-KL-Pad6)") (class "Default")
      (node (ref "X11") (pin "6") (pinfunction "KL_6") (pintype "passive"))
    )
    (net (code "224") (name "unconnected-(X11H-KL-Pad7)") (class "Default")
      (node (ref "X11") (pin "7") (pinfunction "KL_7") (pintype "passive"))
    )
    (net (code "225") (name "unconnected-(X11I-KL-Pad8)") (class "Default")
      (node (ref "X11") (pin "8") (pinfunction "KL_8") (pintype "passive"))
    )
  )
)
